# WordClock_LED_Display.net
KiCad netlist of a schematic drawn in Altium Designer
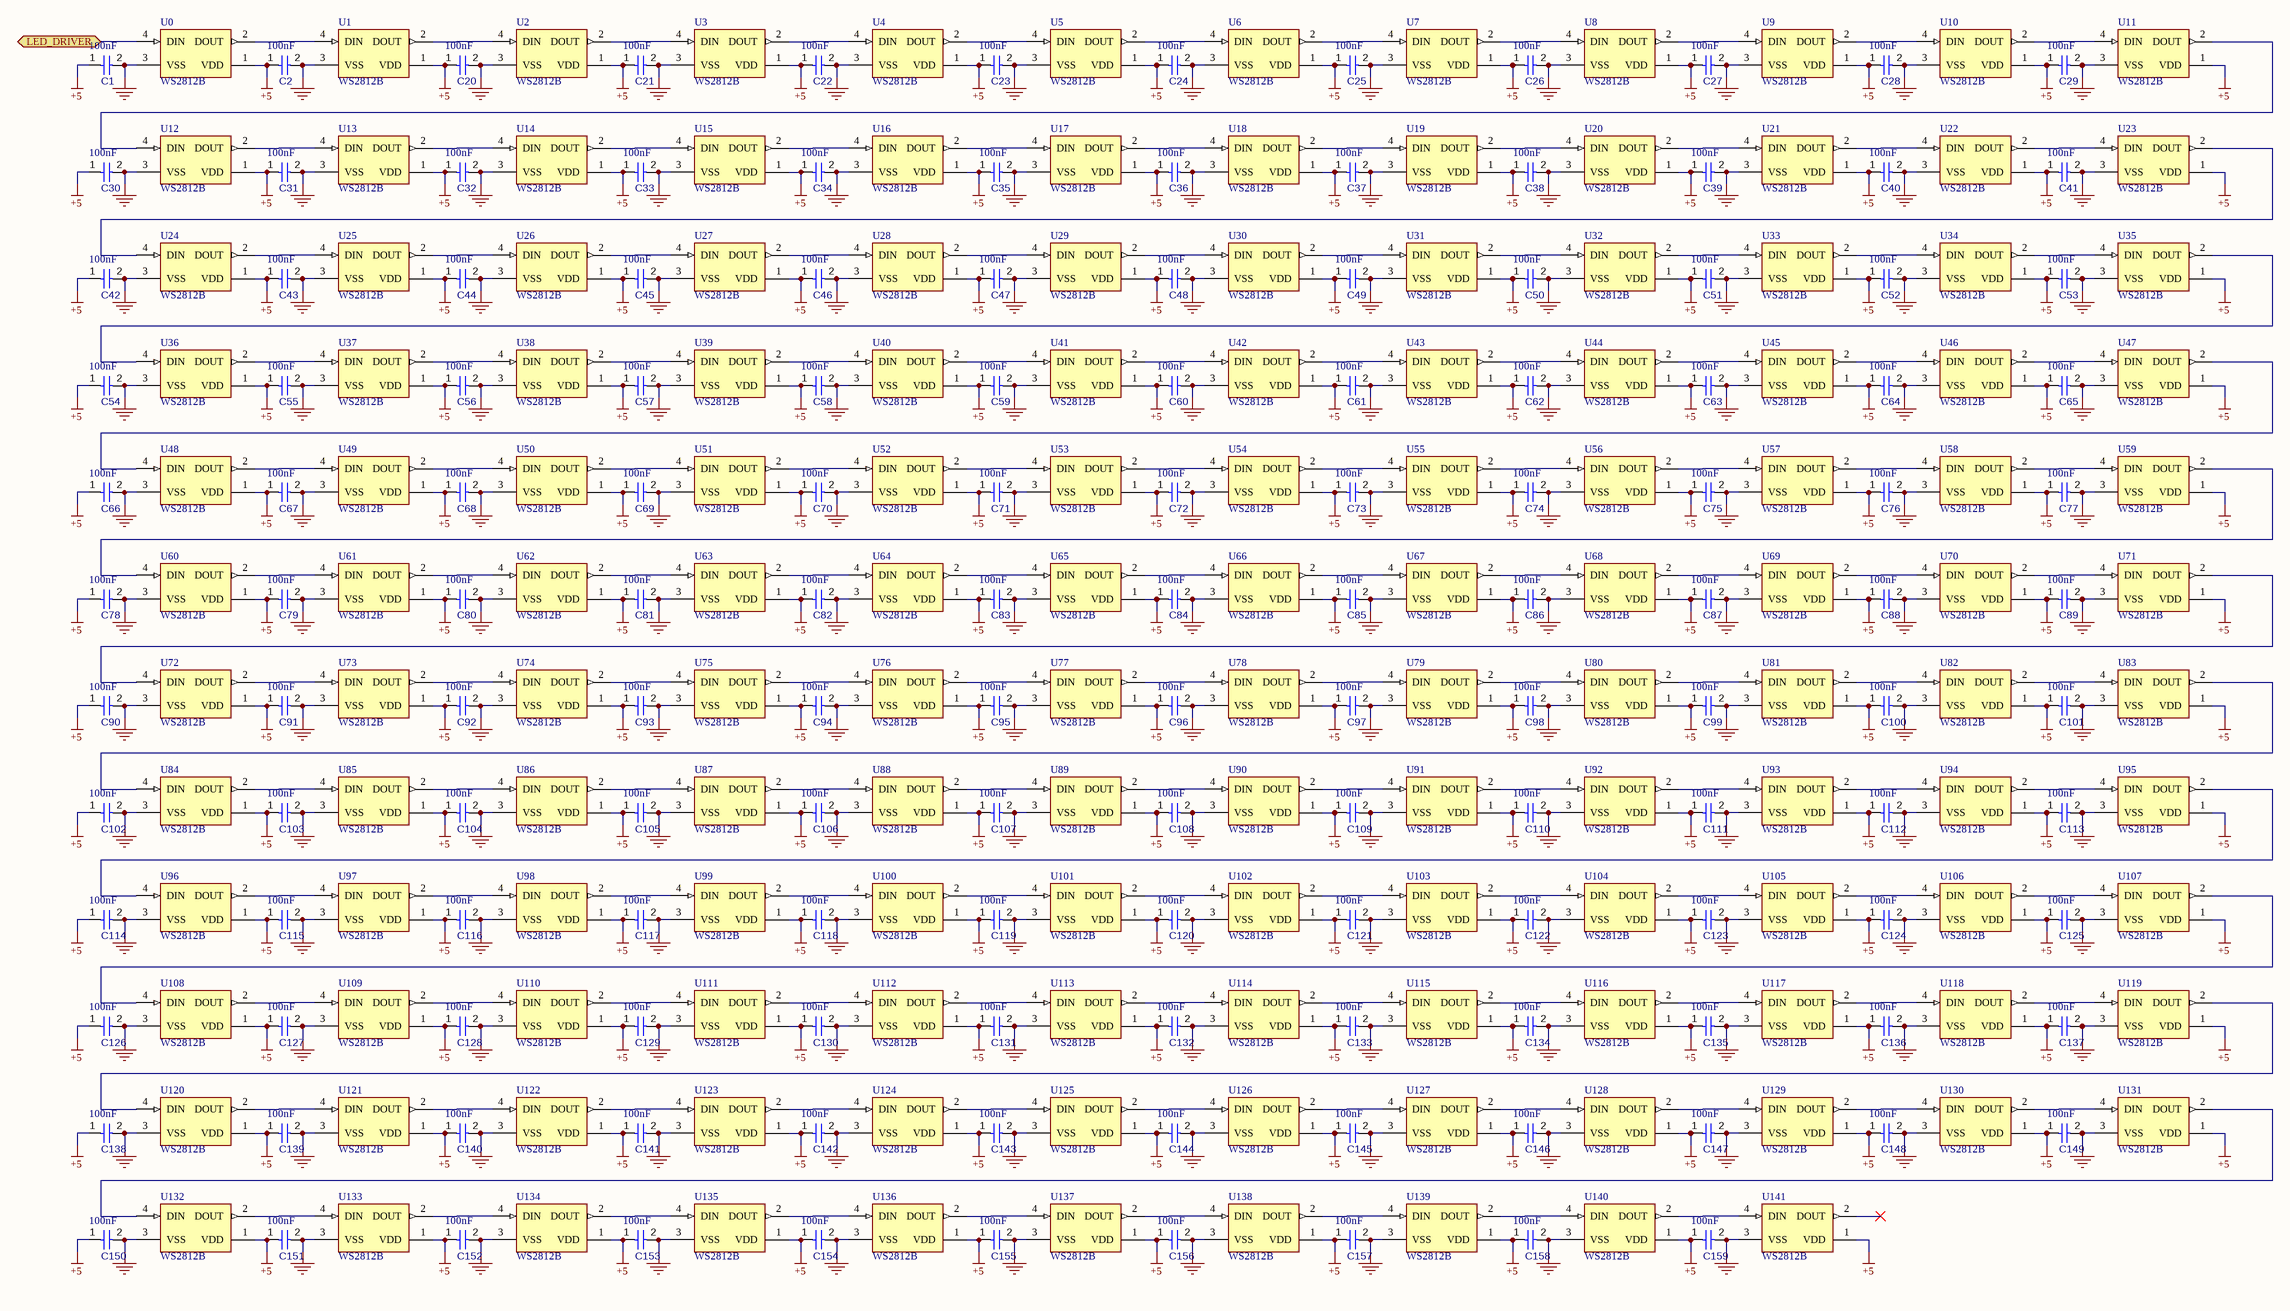
[diagram p0: WordClock_LED_Display.SchDoc]

(export (version "E")
  (design (tool "Eeschema 10.0.6"))
  (components
    (comp (ref "C1")
      (value "100nF")
      (footprint "CAPC0402(1005)60_L")
      (description "Chip Capacitor, 100nF +/-20%, 25V, 0402, Thickness 0.6 mm")
      (fields (field (name "TOLERANCE") "10%") (field (name "Comment") "Capacitor 100nF +/-20% 25V 0402"))
      (libsource (lib "Southwestern College") (part "CAP-NP-2"))
    )
    (comp (ref "C2")
      (value "100nF")
      (footprint "CAPC0402(1005)60_L")
      (description "Chip Capacitor, 100nF +/-20%, 25V, 0402, Thickness 0.6 mm")
      (fields (field (name "TOLERANCE") "10%") (field (name "Comment") "Capacitor 100nF +/-20% 25V 0402"))
      (libsource (lib "Southwestern College") (part "CAP-NP-2"))
    )
    (comp (ref "C20")
      (value "100nF")
      (footprint "CAPC0402(1005)60_L")
      (description "Chip Capacitor, 100nF +/-20%, 25V, 0402, Thickness 0.6 mm")
      (fields (field (name "TOLERANCE") "10%") (field (name "Comment") "Capacitor 100nF +/-20% 25V 0402"))
      (libsource (lib "Southwestern College") (part "CAP-NP-2"))
    )
    (comp (ref "C21")
      (value "100nF")
      (footprint "CAPC0402(1005)60_L")
      (description "Chip Capacitor, 100nF +/-20%, 25V, 0402, Thickness 0.6 mm")
      (fields (field (name "TOLERANCE") "10%") (field (name "Comment") "Capacitor 100nF +/-20% 25V 0402"))
      (libsource (lib "Southwestern College") (part "CAP-NP-2"))
    )
    (comp (ref "C22")
      (value "100nF")
      (footprint "CAPC0402(1005)60_L")
      (description "Chip Capacitor, 100nF +/-20%, 25V, 0402, Thickness 0.6 mm")
      (fields (field (name "TOLERANCE") "10%") (field (name "Comment") "Capacitor 100nF +/-20% 25V 0402"))
      (libsource (lib "Southwestern College") (part "CAP-NP-2"))
    )
    (comp (ref "C23")
      (value "100nF")
      (footprint "CAPC0402(1005)60_L")
      (description "Chip Capacitor, 100nF +/-20%, 25V, 0402, Thickness 0.6 mm")
      (fields (field (name "TOLERANCE") "10%") (field (name "Comment") "Capacitor 100nF +/-20% 25V 0402"))
      (libsource (lib "Southwestern College") (part "CAP-NP-2"))
    )
    (comp (ref "C24")
      (value "100nF")
      (footprint "CAPC0402(1005)60_L")
      (description "Chip Capacitor, 100nF +/-20%, 25V, 0402, Thickness 0.6 mm")
      (fields (field (name "TOLERANCE") "10%") (field (name "Comment") "Capacitor 100nF +/-20% 25V 0402"))
      (libsource (lib "Southwestern College") (part "CAP-NP-2"))
    )
    (comp (ref "C25")
      (value "100nF")
      (footprint "CAPC0402(1005)60_L")
      (description "Chip Capacitor, 100nF +/-20%, 25V, 0402, Thickness 0.6 mm")
      (fields (field (name "TOLERANCE") "10%") (field (name "Comment") "Capacitor 100nF +/-20% 25V 0402"))
      (libsource (lib "Southwestern College") (part "CAP-NP-2"))
    )
    (comp (ref "C26")
      (value "100nF")
      (footprint "CAPC0402(1005)60_L")
      (description "Chip Capacitor, 100nF +/-20%, 25V, 0402, Thickness 0.6 mm")
      (fields (field (name "TOLERANCE") "10%") (field (name "Comment") "Capacitor 100nF +/-20% 25V 0402"))
      (libsource (lib "Southwestern College") (part "CAP-NP-2"))
    )
    (comp (ref "C27")
      (value "100nF")
      (footprint "CAPC0402(1005)60_L")
      (description "Chip Capacitor, 100nF +/-20%, 25V, 0402, Thickness 0.6 mm")
      (fields (field (name "TOLERANCE") "10%") (field (name "Comment") "Capacitor 100nF +/-20% 25V 0402"))
      (libsource (lib "Southwestern College") (part "CAP-NP-2"))
    )
    (comp (ref "C28")
      (value "100nF")
      (footprint "CAPC0402(1005)60_L")
      (description "Chip Capacitor, 100nF +/-20%, 25V, 0402, Thickness 0.6 mm")
      (fields (field (name "TOLERANCE") "10%") (field (name "Comment") "Capacitor 100nF +/-20% 25V 0402"))
      (libsource (lib "Southwestern College") (part "CAP-NP-2"))
    )
    (comp (ref "C29")
      (value "100nF")
      (footprint "CAPC0402(1005)60_L")
      (description "Chip Capacitor, 100nF +/-20%, 25V, 0402, Thickness 0.6 mm")
      (fields (field (name "TOLERANCE") "10%") (field (name "Comment") "Capacitor 100nF +/-20% 25V 0402"))
      (libsource (lib "Southwestern College") (part "CAP-NP-2"))
    )
    (comp (ref "C30")
      (value "100nF")
      (footprint "CAPC0402(1005)60_L")
      (description "Chip Capacitor, 100nF +/-20%, 25V, 0402, Thickness 0.6 mm")
      (fields (field (name "TOLERANCE") "10%") (field (name "Comment") "Capacitor 100nF +/-20% 25V 0402"))
      (libsource (lib "Southwestern College") (part "CAP-NP-2"))
    )
    (comp (ref "C31")
      (value "100nF")
      (footprint "CAPC0402(1005)60_L")
      (description "Chip Capacitor, 100nF +/-20%, 25V, 0402, Thickness 0.6 mm")
      (fields (field (name "TOLERANCE") "10%") (field (name "Comment") "Capacitor 100nF +/-20% 25V 0402"))
      (libsource (lib "Southwestern College") (part "CAP-NP-2"))
    )
    (comp (ref "C32")
      (value "100nF")
      (footprint "CAPC0402(1005)60_L")
      (description "Chip Capacitor, 100nF +/-20%, 25V, 0402, Thickness 0.6 mm")
      (fields (field (name "TOLERANCE") "10%") (field (name "Comment") "Capacitor 100nF +/-20% 25V 0402"))
      (libsource (lib "Southwestern College") (part "CAP-NP-2"))
    )
    (comp (ref "C33")
      (value "100nF")
      (footprint "CAPC0402(1005)60_L")
      (description "Chip Capacitor, 100nF +/-20%, 25V, 0402, Thickness 0.6 mm")
      (fields (field (name "TOLERANCE") "10%") (field (name "Comment") "Capacitor 100nF +/-20% 25V 0402"))
      (libsource (lib "Southwestern College") (part "CAP-NP-2"))
    )
    (comp (ref "C34")
      (value "100nF")
      (footprint "CAPC0402(1005)60_L")
      (description "Chip Capacitor, 100nF +/-20%, 25V, 0402, Thickness 0.6 mm")
      (fields (field (name "TOLERANCE") "10%") (field (name "Comment") "Capacitor 100nF +/-20% 25V 0402"))
      (libsource (lib "Southwestern College") (part "CAP-NP-2"))
    )
    (comp (ref "C35")
      (value "100nF")
      (footprint "CAPC0402(1005)60_L")
      (description "Chip Capacitor, 100nF +/-20%, 25V, 0402, Thickness 0.6 mm")
      (fields (field (name "TOLERANCE") "10%") (field (name "Comment") "Capacitor 100nF +/-20% 25V 0402"))
      (libsource (lib "Southwestern College") (part "CAP-NP-2"))
    )
    (comp (ref "C36")
      (value "100nF")
      (footprint "CAPC0402(1005)60_L")
      (description "Chip Capacitor, 100nF +/-20%, 25V, 0402, Thickness 0.6 mm")
      (fields (field (name "TOLERANCE") "10%") (field (name "Comment") "Capacitor 100nF +/-20% 25V 0402"))
      (libsource (lib "Southwestern College") (part "CAP-NP-2"))
    )
    (comp (ref "C37")
      (value "100nF")
      (footprint "CAPC0402(1005)60_L")
      (description "Chip Capacitor, 100nF +/-20%, 25V, 0402, Thickness 0.6 mm")
      (fields (field (name "TOLERANCE") "10%") (field (name "Comment") "Capacitor 100nF +/-20% 25V 0402"))
      (libsource (lib "Southwestern College") (part "CAP-NP-2"))
    )
    (comp (ref "C38")
      (value "100nF")
      (footprint "CAPC0402(1005)60_L")
      (description "Chip Capacitor, 100nF +/-20%, 25V, 0402, Thickness 0.6 mm")
      (fields (field (name "TOLERANCE") "10%") (field (name "Comment") "Capacitor 100nF +/-20% 25V 0402"))
      (libsource (lib "Southwestern College") (part "CAP-NP-2"))
    )
    (comp (ref "C39")
      (value "100nF")
      (footprint "CAPC0402(1005)60_L")
      (description "Chip Capacitor, 100nF +/-20%, 25V, 0402, Thickness 0.6 mm")
      (fields (field (name "TOLERANCE") "10%") (field (name "Comment") "Capacitor 100nF +/-20% 25V 0402"))
      (libsource (lib "Southwestern College") (part "CAP-NP-2"))
    )
    (comp (ref "C40")
      (value "100nF")
      (footprint "CAPC0402(1005)60_L")
      (description "Chip Capacitor, 100nF +/-20%, 25V, 0402, Thickness 0.6 mm")
      (fields (field (name "TOLERANCE") "10%") (field (name "Comment") "Capacitor 100nF +/-20% 25V 0402"))
      (libsource (lib "Southwestern College") (part "CAP-NP-2"))
    )
    (comp (ref "C41")
      (value "100nF")
      (footprint "CAPC0402(1005)60_L")
      (description "Chip Capacitor, 100nF +/-20%, 25V, 0402, Thickness 0.6 mm")
      (fields (field (name "TOLERANCE") "10%") (field (name "Comment") "Capacitor 100nF +/-20% 25V 0402"))
      (libsource (lib "Southwestern College") (part "CAP-NP-2"))
    )
    (comp (ref "C42")
      (value "100nF")
      (footprint "CAPC0402(1005)60_L")
      (description "Chip Capacitor, 100nF +/-20%, 25V, 0402, Thickness 0.6 mm")
      (fields (field (name "TOLERANCE") "10%") (field (name "Comment") "Capacitor 100nF +/-20% 25V 0402"))
      (libsource (lib "Southwestern College") (part "CAP-NP-2"))
    )
    (comp (ref "C43")
      (value "100nF")
      (footprint "CAPC0402(1005)60_L")
      (description "Chip Capacitor, 100nF +/-20%, 25V, 0402, Thickness 0.6 mm")
      (fields (field (name "TOLERANCE") "10%") (field (name "Comment") "Capacitor 100nF +/-20% 25V 0402"))
      (libsource (lib "Southwestern College") (part "CAP-NP-2"))
    )
    (comp (ref "C44")
      (value "100nF")
      (footprint "CAPC0402(1005)60_L")
      (description "Chip Capacitor, 100nF +/-20%, 25V, 0402, Thickness 0.6 mm")
      (fields (field (name "TOLERANCE") "10%") (field (name "Comment") "Capacitor 100nF +/-20% 25V 0402"))
      (libsource (lib "Southwestern College") (part "CAP-NP-2"))
    )
    (comp (ref "C45")
      (value "100nF")
      (footprint "CAPC0402(1005)60_L")
      (description "Chip Capacitor, 100nF +/-20%, 25V, 0402, Thickness 0.6 mm")
      (fields (field (name "TOLERANCE") "10%") (field (name "Comment") "Capacitor 100nF +/-20% 25V 0402"))
      (libsource (lib "Southwestern College") (part "CAP-NP-2"))
    )
    (comp (ref "C46")
      (value "100nF")
      (footprint "CAPC0402(1005)60_L")
      (description "Chip Capacitor, 100nF +/-20%, 25V, 0402, Thickness 0.6 mm")
      (fields (field (name "TOLERANCE") "10%") (field (name "Comment") "Capacitor 100nF +/-20% 25V 0402"))
      (libsource (lib "Southwestern College") (part "CAP-NP-2"))
    )
    (comp (ref "C47")
      (value "100nF")
      (footprint "CAPC0402(1005)60_L")
      (description "Chip Capacitor, 100nF +/-20%, 25V, 0402, Thickness 0.6 mm")
      (fields (field (name "TOLERANCE") "10%") (field (name "Comment") "Capacitor 100nF +/-20% 25V 0402"))
      (libsource (lib "Southwestern College") (part "CAP-NP-2"))
    )
    (comp (ref "C48")
      (value "100nF")
      (footprint "CAPC0402(1005)60_L")
      (description "Chip Capacitor, 100nF +/-20%, 25V, 0402, Thickness 0.6 mm")
      (fields (field (name "TOLERANCE") "10%") (field (name "Comment") "Capacitor 100nF +/-20% 25V 0402"))
      (libsource (lib "Southwestern College") (part "CAP-NP-2"))
    )
    (comp (ref "C49")
      (value "100nF")
      (footprint "CAPC0402(1005)60_L")
      (description "Chip Capacitor, 100nF +/-20%, 25V, 0402, Thickness 0.6 mm")
      (fields (field (name "TOLERANCE") "10%") (field (name "Comment") "Capacitor 100nF +/-20% 25V 0402"))
      (libsource (lib "Southwestern College") (part "CAP-NP-2"))
    )
    (comp (ref "C50")
      (value "100nF")
      (footprint "CAPC0402(1005)60_L")
      (description "Chip Capacitor, 100nF +/-20%, 25V, 0402, Thickness 0.6 mm")
      (fields (field (name "TOLERANCE") "10%") (field (name "Comment") "Capacitor 100nF +/-20% 25V 0402"))
      (libsource (lib "Southwestern College") (part "CAP-NP-2"))
    )
    (comp (ref "C51")
      (value "100nF")
      (footprint "CAPC0402(1005)60_L")
      (description "Chip Capacitor, 100nF +/-20%, 25V, 0402, Thickness 0.6 mm")
      (fields (field (name "TOLERANCE") "10%") (field (name "Comment") "Capacitor 100nF +/-20% 25V 0402"))
      (libsource (lib "Southwestern College") (part "CAP-NP-2"))
    )
    (comp (ref "C52")
      (value "100nF")
      (footprint "CAPC0402(1005)60_L")
      (description "Chip Capacitor, 100nF +/-20%, 25V, 0402, Thickness 0.6 mm")
      (fields (field (name "TOLERANCE") "10%") (field (name "Comment") "Capacitor 100nF +/-20% 25V 0402"))
      (libsource (lib "Southwestern College") (part "CAP-NP-2"))
    )
    (comp (ref "C53")
      (value "100nF")
      (footprint "CAPC0402(1005)60_L")
      (description "Chip Capacitor, 100nF +/-20%, 25V, 0402, Thickness 0.6 mm")
      (fields (field (name "TOLERANCE") "10%") (field (name "Comment") "Capacitor 100nF +/-20% 25V 0402"))
      (libsource (lib "Southwestern College") (part "CAP-NP-2"))
    )
    (comp (ref "C54")
      (value "100nF")
      (footprint "CAPC0402(1005)60_L")
      (description "Chip Capacitor, 100nF +/-20%, 25V, 0402, Thickness 0.6 mm")
      (fields (field (name "TOLERANCE") "10%") (field (name "Comment") "Capacitor 100nF +/-20% 25V 0402"))
      (libsource (lib "Southwestern College") (part "CAP-NP-2"))
    )
    (comp (ref "C55")
      (value "100nF")
      (footprint "CAPC0402(1005)60_L")
      (description "Chip Capacitor, 100nF +/-20%, 25V, 0402, Thickness 0.6 mm")
      (fields (field (name "TOLERANCE") "10%") (field (name "Comment") "Capacitor 100nF +/-20% 25V 0402"))
      (libsource (lib "Southwestern College") (part "CAP-NP-2"))
    )
    (comp (ref "C56")
      (value "100nF")
      (footprint "CAPC0402(1005)60_L")
      (description "Chip Capacitor, 100nF +/-20%, 25V, 0402, Thickness 0.6 mm")
      (fields (field (name "TOLERANCE") "10%") (field (name "Comment") "Capacitor 100nF +/-20% 25V 0402"))
      (libsource (lib "Southwestern College") (part "CAP-NP-2"))
    )
    (comp (ref "C57")
      (value "100nF")
      (footprint "CAPC0402(1005)60_L")
      (description "Chip Capacitor, 100nF +/-20%, 25V, 0402, Thickness 0.6 mm")
      (fields (field (name "TOLERANCE") "10%") (field (name "Comment") "Capacitor 100nF +/-20% 25V 0402"))
      (libsource (lib "Southwestern College") (part "CAP-NP-2"))
    )
    (comp (ref "C58")
      (value "100nF")
      (footprint "CAPC0402(1005)60_L")
      (description "Chip Capacitor, 100nF +/-20%, 25V, 0402, Thickness 0.6 mm")
      (fields (field (name "TOLERANCE") "10%") (field (name "Comment") "Capacitor 100nF +/-20% 25V 0402"))
      (libsource (lib "Southwestern College") (part "CAP-NP-2"))
    )
    (comp (ref "C59")
      (value "100nF")
      (footprint "CAPC0402(1005)60_L")
      (description "Chip Capacitor, 100nF +/-20%, 25V, 0402, Thickness 0.6 mm")
      (fields (field (name "TOLERANCE") "10%") (field (name "Comment") "Capacitor 100nF +/-20% 25V 0402"))
      (libsource (lib "Southwestern College") (part "CAP-NP-2"))
    )
    (comp (ref "C60")
      (value "100nF")
      (footprint "CAPC0402(1005)60_L")
      (description "Chip Capacitor, 100nF +/-20%, 25V, 0402, Thickness 0.6 mm")
      (fields (field (name "TOLERANCE") "10%") (field (name "Comment") "Capacitor 100nF +/-20% 25V 0402"))
      (libsource (lib "Southwestern College") (part "CAP-NP-2"))
    )
    (comp (ref "C61")
      (value "100nF")
      (footprint "CAPC0402(1005)60_L")
      (description "Chip Capacitor, 100nF +/-20%, 25V, 0402, Thickness 0.6 mm")
      (fields (field (name "TOLERANCE") "10%") (field (name "Comment") "Capacitor 100nF +/-20% 25V 0402"))
      (libsource (lib "Southwestern College") (part "CAP-NP-2"))
    )
    (comp (ref "C62")
      (value "100nF")
      (footprint "CAPC0402(1005)60_L")
      (description "Chip Capacitor, 100nF +/-20%, 25V, 0402, Thickness 0.6 mm")
      (fields (field (name "TOLERANCE") "10%") (field (name "Comment") "Capacitor 100nF +/-20% 25V 0402"))
      (libsource (lib "Southwestern College") (part "CAP-NP-2"))
    )
    (comp (ref "C63")
      (value "100nF")
      (footprint "CAPC0402(1005)60_L")
      (description "Chip Capacitor, 100nF +/-20%, 25V, 0402, Thickness 0.6 mm")
      (fields (field (name "TOLERANCE") "10%") (field (name "Comment") "Capacitor 100nF +/-20% 25V 0402"))
      (libsource (lib "Southwestern College") (part "CAP-NP-2"))
    )
    (comp (ref "C64")
      (value "100nF")
      (footprint "CAPC0402(1005)60_L")
      (description "Chip Capacitor, 100nF +/-20%, 25V, 0402, Thickness 0.6 mm")
      (fields (field (name "TOLERANCE") "10%") (field (name "Comment") "Capacitor 100nF +/-20% 25V 0402"))
      (libsource (lib "Southwestern College") (part "CAP-NP-2"))
    )
    (comp (ref "C65")
      (value "100nF")
      (footprint "CAPC0402(1005)60_L")
      (description "Chip Capacitor, 100nF +/-20%, 25V, 0402, Thickness 0.6 mm")
      (fields (field (name "TOLERANCE") "10%") (field (name "Comment") "Capacitor 100nF +/-20% 25V 0402"))
      (libsource (lib "Southwestern College") (part "CAP-NP-2"))
    )
    (comp (ref "C66")
      (value "100nF")
      (footprint "CAPC0402(1005)60_L")
      (description "Chip Capacitor, 100nF +/-20%, 25V, 0402, Thickness 0.6 mm")
      (fields (field (name "TOLERANCE") "10%") (field (name "Comment") "Capacitor 100nF +/-20% 25V 0402"))
      (libsource (lib "Southwestern College") (part "CAP-NP-2"))
    )
    (comp (ref "C67")
      (value "100nF")
      (footprint "CAPC0402(1005)60_L")
      (description "Chip Capacitor, 100nF +/-20%, 25V, 0402, Thickness 0.6 mm")
      (fields (field (name "TOLERANCE") "10%") (field (name "Comment") "Capacitor 100nF +/-20% 25V 0402"))
      (libsource (lib "Southwestern College") (part "CAP-NP-2"))
    )
    (comp (ref "C68")
      (value "100nF")
      (footprint "CAPC0402(1005)60_L")
      (description "Chip Capacitor, 100nF +/-20%, 25V, 0402, Thickness 0.6 mm")
      (fields (field (name "TOLERANCE") "10%") (field (name "Comment") "Capacitor 100nF +/-20% 25V 0402"))
      (libsource (lib "Southwestern College") (part "CAP-NP-2"))
    )
    (comp (ref "C69")
      (value "100nF")
      (footprint "CAPC0402(1005)60_L")
      (description "Chip Capacitor, 100nF +/-20%, 25V, 0402, Thickness 0.6 mm")
      (fields (field (name "TOLERANCE") "10%") (field (name "Comment") "Capacitor 100nF +/-20% 25V 0402"))
      (libsource (lib "Southwestern College") (part "CAP-NP-2"))
    )
    (comp (ref "C70")
      (value "100nF")
      (footprint "CAPC0402(1005)60_L")
      (description "Chip Capacitor, 100nF +/-20%, 25V, 0402, Thickness 0.6 mm")
      (fields (field (name "TOLERANCE") "10%") (field (name "Comment") "Capacitor 100nF +/-20% 25V 0402"))
      (libsource (lib "Southwestern College") (part "CAP-NP-2"))
    )
    (comp (ref "C71")
      (value "100nF")
      (footprint "CAPC0402(1005)60_L")
      (description "Chip Capacitor, 100nF +/-20%, 25V, 0402, Thickness 0.6 mm")
      (fields (field (name "TOLERANCE") "10%") (field (name "Comment") "Capacitor 100nF +/-20% 25V 0402"))
      (libsource (lib "Southwestern College") (part "CAP-NP-2"))
    )
    (comp (ref "C72")
      (value "100nF")
      (footprint "CAPC0402(1005)60_L")
      (description "Chip Capacitor, 100nF +/-20%, 25V, 0402, Thickness 0.6 mm")
      (fields (field (name "TOLERANCE") "10%") (field (name "Comment") "Capacitor 100nF +/-20% 25V 0402"))
      (libsource (lib "Southwestern College") (part "CAP-NP-2"))
    )
    (comp (ref "C73")
      (value "100nF")
      (footprint "CAPC0402(1005)60_L")
      (description "Chip Capacitor, 100nF +/-20%, 25V, 0402, Thickness 0.6 mm")
      (fields (field (name "TOLERANCE") "10%") (field (name "Comment") "Capacitor 100nF +/-20% 25V 0402"))
      (libsource (lib "Southwestern College") (part "CAP-NP-2"))
    )
    (comp (ref "C74")
      (value "100nF")
      (footprint "CAPC0402(1005)60_L")
      (description "Chip Capacitor, 100nF +/-20%, 25V, 0402, Thickness 0.6 mm")
      (fields (field (name "TOLERANCE") "10%") (field (name "Comment") "Capacitor 100nF +/-20% 25V 0402"))
      (libsource (lib "Southwestern College") (part "CAP-NP-2"))
    )
    (comp (ref "C75")
      (value "100nF")
      (footprint "CAPC0402(1005)60_L")
      (description "Chip Capacitor, 100nF +/-20%, 25V, 0402, Thickness 0.6 mm")
      (fields (field (name "TOLERANCE") "10%") (field (name "Comment") "Capacitor 100nF +/-20% 25V 0402"))
      (libsource (lib "Southwestern College") (part "CAP-NP-2"))
    )
    (comp (ref "C76")
      (value "100nF")
      (footprint "CAPC0402(1005)60_L")
      (description "Chip Capacitor, 100nF +/-20%, 25V, 0402, Thickness 0.6 mm")
      (fields (field (name "TOLERANCE") "10%") (field (name "Comment") "Capacitor 100nF +/-20% 25V 0402"))
      (libsource (lib "Southwestern College") (part "CAP-NP-2"))
    )
    (comp (ref "C77")
      (value "100nF")
      (footprint "CAPC0402(1005)60_L")
      (description "Chip Capacitor, 100nF +/-20%, 25V, 0402, Thickness 0.6 mm")
      (fields (field (name "TOLERANCE") "10%") (field (name "Comment") "Capacitor 100nF +/-20% 25V 0402"))
      (libsource (lib "Southwestern College") (part "CAP-NP-2"))
    )
    (comp (ref "C78")
      (value "100nF")
      (footprint "CAPC0402(1005)60_L")
      (description "Chip Capacitor, 100nF +/-20%, 25V, 0402, Thickness 0.6 mm")
      (fields (field (name "TOLERANCE") "10%") (field (name "Comment") "Capacitor 100nF +/-20% 25V 0402"))
      (libsource (lib "Southwestern College") (part "CAP-NP-2"))
    )
    (comp (ref "C79")
      (value "100nF")
      (footprint "CAPC0402(1005)60_L")
      (description "Chip Capacitor, 100nF +/-20%, 25V, 0402, Thickness 0.6 mm")
      (fields (field (name "TOLERANCE") "10%") (field (name "Comment") "Capacitor 100nF +/-20% 25V 0402"))
      (libsource (lib "Southwestern College") (part "CAP-NP-2"))
    )
    (comp (ref "C80")
      (value "100nF")
      (footprint "CAPC0402(1005)60_L")
      (description "Chip Capacitor, 100nF +/-20%, 25V, 0402, Thickness 0.6 mm")
      (fields (field (name "TOLERANCE") "10%") (field (name "Comment") "Capacitor 100nF +/-20% 25V 0402"))
      (libsource (lib "Southwestern College") (part "CAP-NP-2"))
    )
    (comp (ref "C81")
      (value "100nF")
      (footprint "CAPC0402(1005)60_L")
      (description "Chip Capacitor, 100nF +/-20%, 25V, 0402, Thickness 0.6 mm")
      (fields (field (name "TOLERANCE") "10%") (field (name "Comment") "Capacitor 100nF +/-20% 25V 0402"))
      (libsource (lib "Southwestern College") (part "CAP-NP-2"))
    )
    (comp (ref "C82")
      (value "100nF")
      (footprint "CAPC0402(1005)60_L")
      (description "Chip Capacitor, 100nF +/-20%, 25V, 0402, Thickness 0.6 mm")
      (fields (field (name "TOLERANCE") "10%") (field (name "Comment") "Capacitor 100nF +/-20% 25V 0402"))
      (libsource (lib "Southwestern College") (part "CAP-NP-2"))
    )
    (comp (ref "C83")
      (value "100nF")
      (footprint "CAPC0402(1005)60_L")
      (description "Chip Capacitor, 100nF +/-20%, 25V, 0402, Thickness 0.6 mm")
      (fields (field (name "TOLERANCE") "10%") (field (name "Comment") "Capacitor 100nF +/-20% 25V 0402"))
      (libsource (lib "Southwestern College") (part "CAP-NP-2"))
    )
    (comp (ref "C84")
      (value "100nF")
      (footprint "CAPC0402(1005)60_L")
      (description "Chip Capacitor, 100nF +/-20%, 25V, 0402, Thickness 0.6 mm")
      (fields (field (name "TOLERANCE") "10%") (field (name "Comment") "Capacitor 100nF +/-20% 25V 0402"))
      (libsource (lib "Southwestern College") (part "CAP-NP-2"))
    )
    (comp (ref "C85")
      (value "100nF")
      (footprint "CAPC0402(1005)60_L")
      (description "Chip Capacitor, 100nF +/-20%, 25V, 0402, Thickness 0.6 mm")
      (fields (field (name "TOLERANCE") "10%") (field (name "Comment") "Capacitor 100nF +/-20% 25V 0402"))
      (libsource (lib "Southwestern College") (part "CAP-NP-2"))
    )
    (comp (ref "C86")
      (value "100nF")
      (footprint "CAPC0402(1005)60_L")
      (description "Chip Capacitor, 100nF +/-20%, 25V, 0402, Thickness 0.6 mm")
      (fields (field (name "TOLERANCE") "10%") (field (name "Comment") "Capacitor 100nF +/-20% 25V 0402"))
      (libsource (lib "Southwestern College") (part "CAP-NP-2"))
    )
    (comp (ref "C87")
      (value "100nF")
      (footprint "CAPC0402(1005)60_L")
      (description "Chip Capacitor, 100nF +/-20%, 25V, 0402, Thickness 0.6 mm")
      (fields (field (name "TOLERANCE") "10%") (field (name "Comment") "Capacitor 100nF +/-20% 25V 0402"))
      (libsource (lib "Southwestern College") (part "CAP-NP-2"))
    )
    (comp (ref "C88")
      (value "100nF")
      (footprint "CAPC0402(1005)60_L")
      (description "Chip Capacitor, 100nF +/-20%, 25V, 0402, Thickness 0.6 mm")
      (fields (field (name "TOLERANCE") "10%") (field (name "Comment") "Capacitor 100nF +/-20% 25V 0402"))
      (libsource (lib "Southwestern College") (part "CAP-NP-2"))
    )
    (comp (ref "C89")
      (value "100nF")
      (footprint "CAPC0402(1005)60_L")
      (description "Chip Capacitor, 100nF +/-20%, 25V, 0402, Thickness 0.6 mm")
      (fields (field (name "TOLERANCE") "10%") (field (name "Comment") "Capacitor 100nF +/-20% 25V 0402"))
      (libsource (lib "Southwestern College") (part "CAP-NP-2"))
    )
    (comp (ref "C90")
      (value "100nF")
      (footprint "CAPC0402(1005)60_L")
      (description "Chip Capacitor, 100nF +/-20%, 25V, 0402, Thickness 0.6 mm")
      (fields (field (name "TOLERANCE") "10%") (field (name "Comment") "Capacitor 100nF +/-20% 25V 0402"))
      (libsource (lib "Southwestern College") (part "CAP-NP-2"))
    )
    (comp (ref "C91")
      (value "100nF")
      (footprint "CAPC0402(1005)60_L")
      (description "Chip Capacitor, 100nF +/-20%, 25V, 0402, Thickness 0.6 mm")
      (fields (field (name "TOLERANCE") "10%") (field (name "Comment") "Capacitor 100nF +/-20% 25V 0402"))
      (libsource (lib "Southwestern College") (part "CAP-NP-2"))
    )
    (comp (ref "C92")
      (value "100nF")
      (footprint "CAPC0402(1005)60_L")
      (description "Chip Capacitor, 100nF +/-20%, 25V, 0402, Thickness 0.6 mm")
      (fields (field (name "TOLERANCE") "10%") (field (name "Comment") "Capacitor 100nF +/-20% 25V 0402"))
      (libsource (lib "Southwestern College") (part "CAP-NP-2"))
    )
    (comp (ref "C93")
      (value "100nF")
      (footprint "CAPC0402(1005)60_L")
      (description "Chip Capacitor, 100nF +/-20%, 25V, 0402, Thickness 0.6 mm")
      (fields (field (name "TOLERANCE") "10%") (field (name "Comment") "Capacitor 100nF +/-20% 25V 0402"))
      (libsource (lib "Southwestern College") (part "CAP-NP-2"))
    )
    (comp (ref "C94")
      (value "100nF")
      (footprint "CAPC0402(1005)60_L")
      (description "Chip Capacitor, 100nF +/-20%, 25V, 0402, Thickness 0.6 mm")
      (fields (field (name "TOLERANCE") "10%") (field (name "Comment") "Capacitor 100nF +/-20% 25V 0402"))
      (libsource (lib "Southwestern College") (part "CAP-NP-2"))
    )
    (comp (ref "C95")
      (value "100nF")
      (footprint "CAPC0402(1005)60_L")
      (description "Chip Capacitor, 100nF +/-20%, 25V, 0402, Thickness 0.6 mm")
      (fields (field (name "TOLERANCE") "10%") (field (name "Comment") "Capacitor 100nF +/-20% 25V 0402"))
      (libsource (lib "Southwestern College") (part "CAP-NP-2"))
    )
    (comp (ref "C96")
      (value "100nF")
      (footprint "CAPC0402(1005)60_L")
      (description "Chip Capacitor, 100nF +/-20%, 25V, 0402, Thickness 0.6 mm")
      (fields (field (name "TOLERANCE") "10%") (field (name "Comment") "Capacitor 100nF +/-20% 25V 0402"))
      (libsource (lib "Southwestern College") (part "CAP-NP-2"))
    )
    (comp (ref "C97")
      (value "100nF")
      (footprint "CAPC0402(1005)60_L")
      (description "Chip Capacitor, 100nF +/-20%, 25V, 0402, Thickness 0.6 mm")
      (fields (field (name "TOLERANCE") "10%") (field (name "Comment") "Capacitor 100nF +/-20% 25V 0402"))
      (libsource (lib "Southwestern College") (part "CAP-NP-2"))
    )
    (comp (ref "C98")
      (value "100nF")
      (footprint "CAPC0402(1005)60_L")
      (description "Chip Capacitor, 100nF +/-20%, 25V, 0402, Thickness 0.6 mm")
      (fields (field (name "TOLERANCE") "10%") (field (name "Comment") "Capacitor 100nF +/-20% 25V 0402"))
      (libsource (lib "Southwestern College") (part "CAP-NP-2"))
    )
    (comp (ref "C99")
      (value "100nF")
      (footprint "CAPC0402(1005)60_L")
      (description "Chip Capacitor, 100nF +/-20%, 25V, 0402, Thickness 0.6 mm")
      (fields (field (name "TOLERANCE") "10%") (field (name "Comment") "Capacitor 100nF +/-20% 25V 0402"))
      (libsource (lib "Southwestern College") (part "CAP-NP-2"))
    )
    (comp (ref "C100")
      (value "100nF")
      (footprint "CAPC0402(1005)60_L")
      (description "Chip Capacitor, 100nF +/-20%, 25V, 0402, Thickness 0.6 mm")
      (fields (field (name "TOLERANCE") "10%") (field (name "Comment") "Capacitor 100nF +/-20% 25V 0402"))
      (libsource (lib "Southwestern College") (part "CAP-NP-2"))
    )
    (comp (ref "C101")
      (value "100nF")
      (footprint "CAPC0402(1005)60_L")
      (description "Chip Capacitor, 100nF +/-20%, 25V, 0402, Thickness 0.6 mm")
      (fields (field (name "TOLERANCE") "10%") (field (name "Comment") "Capacitor 100nF +/-20% 25V 0402"))
      (libsource (lib "Southwestern College") (part "CAP-NP-2"))
    )
    (comp (ref "C102")
      (value "100nF")
      (footprint "CAPC0402(1005)60_L")
      (description "Chip Capacitor, 100nF +/-20%, 25V, 0402, Thickness 0.6 mm")
      (fields (field (name "TOLERANCE") "10%") (field (name "Comment") "Capacitor 100nF +/-20% 25V 0402"))
      (libsource (lib "Southwestern College") (part "CAP-NP-2"))
    )
    (comp (ref "C103")
      (value "100nF")
      (footprint "CAPC0402(1005)60_L")
      (description "Chip Capacitor, 100nF +/-20%, 25V, 0402, Thickness 0.6 mm")
      (fields (field (name "TOLERANCE") "10%") (field (name "Comment") "Capacitor 100nF +/-20% 25V 0402"))
      (libsource (lib "Southwestern College") (part "CAP-NP-2"))
    )
    (comp (ref "C104")
      (value "100nF")
      (footprint "CAPC0402(1005)60_L")
      (description "Chip Capacitor, 100nF +/-20%, 25V, 0402, Thickness 0.6 mm")
      (fields (field (name "TOLERANCE") "10%") (field (name "Comment") "Capacitor 100nF +/-20% 25V 0402"))
      (libsource (lib "Southwestern College") (part "CAP-NP-2"))
    )
    (comp (ref "C105")
      (value "100nF")
      (footprint "CAPC0402(1005)60_L")
      (description "Chip Capacitor, 100nF +/-20%, 25V, 0402, Thickness 0.6 mm")
      (fields (field (name "TOLERANCE") "10%") (field (name "Comment") "Capacitor 100nF +/-20% 25V 0402"))
      (libsource (lib "Southwestern College") (part "CAP-NP-2"))
    )
    (comp (ref "C106")
      (value "100nF")
      (footprint "CAPC0402(1005)60_L")
      (description "Chip Capacitor, 100nF +/-20%, 25V, 0402, Thickness 0.6 mm")
      (fields (field (name "TOLERANCE") "10%") (field (name "Comment") "Capacitor 100nF +/-20% 25V 0402"))
      (libsource (lib "Southwestern College") (part "CAP-NP-2"))
    )
    (comp (ref "C107")
      (value "100nF")
      (footprint "CAPC0402(1005)60_L")
      (description "Chip Capacitor, 100nF +/-20%, 25V, 0402, Thickness 0.6 mm")
      (fields (field (name "TOLERANCE") "10%") (field (name "Comment") "Capacitor 100nF +/-20% 25V 0402"))
      (libsource (lib "Southwestern College") (part "CAP-NP-2"))
    )
    (comp (ref "C108")
      (value "100nF")
      (footprint "CAPC0402(1005)60_L")
      (description "Chip Capacitor, 100nF +/-20%, 25V, 0402, Thickness 0.6 mm")
      (fields (field (name "TOLERANCE") "10%") (field (name "Comment") "Capacitor 100nF +/-20% 25V 0402"))
      (libsource (lib "Southwestern College") (part "CAP-NP-2"))
    )
    (comp (ref "C109")
      (value "100nF")
      (footprint "CAPC0402(1005)60_L")
      (description "Chip Capacitor, 100nF +/-20%, 25V, 0402, Thickness 0.6 mm")
      (fields (field (name "TOLERANCE") "10%") (field (name "Comment") "Capacitor 100nF +/-20% 25V 0402"))
      (libsource (lib "Southwestern College") (part "CAP-NP-2"))
    )
    (comp (ref "C110")
      (value "100nF")
      (footprint "CAPC0402(1005)60_L")
      (description "Chip Capacitor, 100nF +/-20%, 25V, 0402, Thickness 0.6 mm")
      (fields (field (name "TOLERANCE") "10%") (field (name "Comment") "Capacitor 100nF +/-20% 25V 0402"))
      (libsource (lib "Southwestern College") (part "CAP-NP-2"))
    )
    (comp (ref "C111")
      (value "100nF")
      (footprint "CAPC0402(1005)60_L")
      (description "Chip Capacitor, 100nF +/-20%, 25V, 0402, Thickness 0.6 mm")
      (fields (field (name "TOLERANCE") "10%") (field (name "Comment") "Capacitor 100nF +/-20% 25V 0402"))
      (libsource (lib "Southwestern College") (part "CAP-NP-2"))
    )
    (comp (ref "C112")
      (value "100nF")
      (footprint "CAPC0402(1005)60_L")
      (description "Chip Capacitor, 100nF +/-20%, 25V, 0402, Thickness 0.6 mm")
      (fields (field (name "TOLERANCE") "10%") (field (name "Comment") "Capacitor 100nF +/-20% 25V 0402"))
      (libsource (lib "Southwestern College") (part "CAP-NP-2"))
    )
    (comp (ref "C113")
      (value "100nF")
      (footprint "CAPC0402(1005)60_L")
      (description "Chip Capacitor, 100nF +/-20%, 25V, 0402, Thickness 0.6 mm")
      (fields (field (name "TOLERANCE") "10%") (field (name "Comment") "Capacitor 100nF +/-20% 25V 0402"))
      (libsource (lib "Southwestern College") (part "CAP-NP-2"))
    )
    (comp (ref "C114")
      (value "100nF")
      (footprint "CAPC0402(1005)60_L")
      (description "Chip Capacitor, 100nF +/-20%, 25V, 0402, Thickness 0.6 mm")
      (fields (field (name "TOLERANCE") "10%") (field (name "Comment") "Capacitor 100nF +/-20% 25V 0402"))
      (libsource (lib "Southwestern College") (part "CAP-NP-2"))
    )
    (comp (ref "C115")
      (value "100nF")
      (footprint "CAPC0402(1005)60_L")
      (description "Chip Capacitor, 100nF +/-20%, 25V, 0402, Thickness 0.6 mm")
      (fields (field (name "TOLERANCE") "10%") (field (name "Comment") "Capacitor 100nF +/-20% 25V 0402"))
      (libsource (lib "Southwestern College") (part "CAP-NP-2"))
    )
    (comp (ref "C116")
      (value "100nF")
      (footprint "CAPC0402(1005)60_L")
      (description "Chip Capacitor, 100nF +/-20%, 25V, 0402, Thickness 0.6 mm")
      (fields (field (name "TOLERANCE") "10%") (field (name "Comment") "Capacitor 100nF +/-20% 25V 0402"))
      (libsource (lib "Southwestern College") (part "CAP-NP-2"))
    )
    (comp (ref "C117")
      (value "100nF")
      (footprint "CAPC0402(1005)60_L")
      (description "Chip Capacitor, 100nF +/-20%, 25V, 0402, Thickness 0.6 mm")
      (fields (field (name "TOLERANCE") "10%") (field (name "Comment") "Capacitor 100nF +/-20% 25V 0402"))
      (libsource (lib "Southwestern College") (part "CAP-NP-2"))
    )
    (comp (ref "C118")
      (value "100nF")
      (footprint "CAPC0402(1005)60_L")
      (description "Chip Capacitor, 100nF +/-20%, 25V, 0402, Thickness 0.6 mm")
      (fields (field (name "TOLERANCE") "10%") (field (name "Comment") "Capacitor 100nF +/-20% 25V 0402"))
      (libsource (lib "Southwestern College") (part "CAP-NP-2"))
    )
    (comp (ref "C119")
      (value "100nF")
      (footprint "CAPC0402(1005)60_L")
      (description "Chip Capacitor, 100nF +/-20%, 25V, 0402, Thickness 0.6 mm")
      (fields (field (name "TOLERANCE") "10%") (field (name "Comment") "Capacitor 100nF +/-20% 25V 0402"))
      (libsource (lib "Southwestern College") (part "CAP-NP-2"))
    )
    (comp (ref "C120")
      (value "100nF")
      (footprint "CAPC0402(1005)60_L")
      (description "Chip Capacitor, 100nF +/-20%, 25V, 0402, Thickness 0.6 mm")
      (fields (field (name "TOLERANCE") "10%") (field (name "Comment") "Capacitor 100nF +/-20% 25V 0402"))
      (libsource (lib "Southwestern College") (part "CAP-NP-2"))
    )
    (comp (ref "C121")
      (value "100nF")
      (footprint "CAPC0402(1005)60_L")
      (description "Chip Capacitor, 100nF +/-20%, 25V, 0402, Thickness 0.6 mm")
      (fields (field (name "TOLERANCE") "10%") (field (name "Comment") "Capacitor 100nF +/-20% 25V 0402"))
      (libsource (lib "Southwestern College") (part "CAP-NP-2"))
    )
    (comp (ref "C122")
      (value "100nF")
      (footprint "CAPC0402(1005)60_L")
      (description "Chip Capacitor, 100nF +/-20%, 25V, 0402, Thickness 0.6 mm")
      (fields (field (name "TOLERANCE") "10%") (field (name "Comment") "Capacitor 100nF +/-20% 25V 0402"))
      (libsource (lib "Southwestern College") (part "CAP-NP-2"))
    )
    (comp (ref "C123")
      (value "100nF")
      (footprint "CAPC0402(1005)60_L")
      (description "Chip Capacitor, 100nF +/-20%, 25V, 0402, Thickness 0.6 mm")
      (fields (field (name "TOLERANCE") "10%") (field (name "Comment") "Capacitor 100nF +/-20% 25V 0402"))
      (libsource (lib "Southwestern College") (part "CAP-NP-2"))
    )
    (comp (ref "C124")
      (value "100nF")
      (footprint "CAPC0402(1005)60_L")
      (description "Chip Capacitor, 100nF +/-20%, 25V, 0402, Thickness 0.6 mm")
      (fields (field (name "TOLERANCE") "10%") (field (name "Comment") "Capacitor 100nF +/-20% 25V 0402"))
      (libsource (lib "Southwestern College") (part "CAP-NP-2"))
    )
    (comp (ref "C125")
      (value "100nF")
      (footprint "CAPC0402(1005)60_L")
      (description "Chip Capacitor, 100nF +/-20%, 25V, 0402, Thickness 0.6 mm")
      (fields (field (name "TOLERANCE") "10%") (field (name "Comment") "Capacitor 100nF +/-20% 25V 0402"))
      (libsource (lib "Southwestern College") (part "CAP-NP-2"))
    )
    (comp (ref "C126")
      (value "100nF")
      (footprint "CAPC0402(1005)60_L")
      (description "Chip Capacitor, 100nF +/-20%, 25V, 0402, Thickness 0.6 mm")
      (fields (field (name "TOLERANCE") "10%") (field (name "Comment") "Capacitor 100nF +/-20% 25V 0402"))
      (libsource (lib "Southwestern College") (part "CAP-NP-2"))
    )
    (comp (ref "C127")
      (value "100nF")
      (footprint "CAPC0402(1005)60_L")
      (description "Chip Capacitor, 100nF +/-20%, 25V, 0402, Thickness 0.6 mm")
      (fields (field (name "TOLERANCE") "10%") (field (name "Comment") "Capacitor 100nF +/-20% 25V 0402"))
      (libsource (lib "Southwestern College") (part "CAP-NP-2"))
    )
    (comp (ref "C128")
      (value "100nF")
      (footprint "CAPC0402(1005)60_L")
      (description "Chip Capacitor, 100nF +/-20%, 25V, 0402, Thickness 0.6 mm")
      (fields (field (name "TOLERANCE") "10%") (field (name "Comment") "Capacitor 100nF +/-20% 25V 0402"))
      (libsource (lib "Southwestern College") (part "CAP-NP-2"))
    )
    (comp (ref "C129")
      (value "100nF")
      (footprint "CAPC0402(1005)60_L")
      (description "Chip Capacitor, 100nF +/-20%, 25V, 0402, Thickness 0.6 mm")
      (fields (field (name "TOLERANCE") "10%") (field (name "Comment") "Capacitor 100nF +/-20% 25V 0402"))
      (libsource (lib "Southwestern College") (part "CAP-NP-2"))
    )
    (comp (ref "C130")
      (value "100nF")
      (footprint "CAPC0402(1005)60_L")
      (description "Chip Capacitor, 100nF +/-20%, 25V, 0402, Thickness 0.6 mm")
      (fields (field (name "TOLERANCE") "10%") (field (name "Comment") "Capacitor 100nF +/-20% 25V 0402"))
      (libsource (lib "Southwestern College") (part "CAP-NP-2"))
    )
    (comp (ref "C131")
      (value "100nF")
      (footprint "CAPC0402(1005)60_L")
      (description "Chip Capacitor, 100nF +/-20%, 25V, 0402, Thickness 0.6 mm")
      (fields (field (name "TOLERANCE") "10%") (field (name "Comment") "Capacitor 100nF +/-20% 25V 0402"))
      (libsource (lib "Southwestern College") (part "CAP-NP-2"))
    )
    (comp (ref "C132")
      (value "100nF")
      (footprint "CAPC0402(1005)60_L")
      (description "Chip Capacitor, 100nF +/-20%, 25V, 0402, Thickness 0.6 mm")
      (fields (field (name "TOLERANCE") "10%") (field (name "Comment") "Capacitor 100nF +/-20% 25V 0402"))
      (libsource (lib "Southwestern College") (part "CAP-NP-2"))
    )
    (comp (ref "C133")
      (value "100nF")
      (footprint "CAPC0402(1005)60_L")
      (description "Chip Capacitor, 100nF +/-20%, 25V, 0402, Thickness 0.6 mm")
      (fields (field (name "TOLERANCE") "10%") (field (name "Comment") "Capacitor 100nF +/-20% 25V 0402"))
      (libsource (lib "Southwestern College") (part "CAP-NP-2"))
    )
    (comp (ref "C134")
      (value "100nF")
      (footprint "CAPC0402(1005)60_L")
      (description "Chip Capacitor, 100nF +/-20%, 25V, 0402, Thickness 0.6 mm")
      (fields (field (name "TOLERANCE") "10%") (field (name "Comment") "Capacitor 100nF +/-20% 25V 0402"))
      (libsource (lib "Southwestern College") (part "CAP-NP-2"))
    )
    (comp (ref "C135")
      (value "100nF")
      (footprint "CAPC0402(1005)60_L")
      (description "Chip Capacitor, 100nF +/-20%, 25V, 0402, Thickness 0.6 mm")
      (fields (field (name "TOLERANCE") "10%") (field (name "Comment") "Capacitor 100nF +/-20% 25V 0402"))
      (libsource (lib "Southwestern College") (part "CAP-NP-2"))
    )
    (comp (ref "C136")
      (value "100nF")
      (footprint "CAPC0402(1005)60_L")
      (description "Chip Capacitor, 100nF +/-20%, 25V, 0402, Thickness 0.6 mm")
      (fields (field (name "TOLERANCE") "10%") (field (name "Comment") "Capacitor 100nF +/-20% 25V 0402"))
      (libsource (lib "Southwestern College") (part "CAP-NP-2"))
    )
    (comp (ref "C137")
      (value "100nF")
      (footprint "CAPC0402(1005)60_L")
      (description "Chip Capacitor, 100nF +/-20%, 25V, 0402, Thickness 0.6 mm")
      (fields (field (name "TOLERANCE") "10%") (field (name "Comment") "Capacitor 100nF +/-20% 25V 0402"))
      (libsource (lib "Southwestern College") (part "CAP-NP-2"))
    )
    (comp (ref "C138")
      (value "100nF")
      (footprint "CAPC0402(1005)60_L")
      (description "Chip Capacitor, 100nF +/-20%, 25V, 0402, Thickness 0.6 mm")
      (fields (field (name "TOLERANCE") "10%") (field (name "Comment") "Capacitor 100nF +/-20% 25V 0402"))
      (libsource (lib "Southwestern College") (part "CAP-NP-2"))
    )
    (comp (ref "C139")
      (value "100nF")
      (footprint "CAPC0402(1005)60_L")
      (description "Chip Capacitor, 100nF +/-20%, 25V, 0402, Thickness 0.6 mm")
      (fields (field (name "TOLERANCE") "10%") (field (name "Comment") "Capacitor 100nF +/-20% 25V 0402"))
      (libsource (lib "Southwestern College") (part "CAP-NP-2"))
    )
    (comp (ref "C140")
      (value "100nF")
      (footprint "CAPC0402(1005)60_L")
      (description "Chip Capacitor, 100nF +/-20%, 25V, 0402, Thickness 0.6 mm")
      (fields (field (name "TOLERANCE") "10%") (field (name "Comment") "Capacitor 100nF +/-20% 25V 0402"))
      (libsource (lib "Southwestern College") (part "CAP-NP-2"))
    )
    (comp (ref "C141")
      (value "100nF")
      (footprint "CAPC0402(1005)60_L")
      (description "Chip Capacitor, 100nF +/-20%, 25V, 0402, Thickness 0.6 mm")
      (fields (field (name "TOLERANCE") "10%") (field (name "Comment") "Capacitor 100nF +/-20% 25V 0402"))
      (libsource (lib "Southwestern College") (part "CAP-NP-2"))
    )
    (comp (ref "C142")
      (value "100nF")
      (footprint "CAPC0402(1005)60_L")
      (description "Chip Capacitor, 100nF +/-20%, 25V, 0402, Thickness 0.6 mm")
      (fields (field (name "TOLERANCE") "10%") (field (name "Comment") "Capacitor 100nF +/-20% 25V 0402"))
      (libsource (lib "Southwestern College") (part "CAP-NP-2"))
    )
    (comp (ref "C143")
      (value "100nF")
      (footprint "CAPC0402(1005)60_L")
      (description "Chip Capacitor, 100nF +/-20%, 25V, 0402, Thickness 0.6 mm")
      (fields (field (name "TOLERANCE") "10%") (field (name "Comment") "Capacitor 100nF +/-20% 25V 0402"))
      (libsource (lib "Southwestern College") (part "CAP-NP-2"))
    )
    (comp (ref "C144")
      (value "100nF")
      (footprint "CAPC0402(1005)60_L")
      (description "Chip Capacitor, 100nF +/-20%, 25V, 0402, Thickness 0.6 mm")
      (fields (field (name "TOLERANCE") "10%") (field (name "Comment") "Capacitor 100nF +/-20% 25V 0402"))
      (libsource (lib "Southwestern College") (part "CAP-NP-2"))
    )
    (comp (ref "C145")
      (value "100nF")
      (footprint "CAPC0402(1005)60_L")
      (description "Chip Capacitor, 100nF +/-20%, 25V, 0402, Thickness 0.6 mm")
      (fields (field (name "TOLERANCE") "10%") (field (name "Comment") "Capacitor 100nF +/-20% 25V 0402"))
      (libsource (lib "Southwestern College") (part "CAP-NP-2"))
    )
    (comp (ref "C146")
      (value "100nF")
      (footprint "CAPC0402(1005)60_L")
      (description "Chip Capacitor, 100nF +/-20%, 25V, 0402, Thickness 0.6 mm")
      (fields (field (name "TOLERANCE") "10%") (field (name "Comment") "Capacitor 100nF +/-20% 25V 0402"))
      (libsource (lib "Southwestern College") (part "CAP-NP-2"))
    )
    (comp (ref "C147")
      (value "100nF")
      (footprint "CAPC0402(1005)60_L")
      (description "Chip Capacitor, 100nF +/-20%, 25V, 0402, Thickness 0.6 mm")
      (fields (field (name "TOLERANCE") "10%") (field (name "Comment") "Capacitor 100nF +/-20% 25V 0402"))
      (libsource (lib "Southwestern College") (part "CAP-NP-2"))
    )
    (comp (ref "C148")
      (value "100nF")
      (footprint "CAPC0402(1005)60_L")
      (description "Chip Capacitor, 100nF +/-20%, 25V, 0402, Thickness 0.6 mm")
      (fields (field (name "TOLERANCE") "10%") (field (name "Comment") "Capacitor 100nF +/-20% 25V 0402"))
      (libsource (lib "Southwestern College") (part "CAP-NP-2"))
    )
    (comp (ref "C149")
      (value "100nF")
      (footprint "CAPC0402(1005)60_L")
      (description "Chip Capacitor, 100nF +/-20%, 25V, 0402, Thickness 0.6 mm")
      (fields (field (name "TOLERANCE") "10%") (field (name "Comment") "Capacitor 100nF +/-20% 25V 0402"))
      (libsource (lib "Southwestern College") (part "CAP-NP-2"))
    )
    (comp (ref "C150")
      (value "100nF")
      (footprint "CAPC0402(1005)60_L")
      (description "Chip Capacitor, 100nF +/-20%, 25V, 0402, Thickness 0.6 mm")
      (fields (field (name "TOLERANCE") "10%") (field (name "Comment") "Capacitor 100nF +/-20% 25V 0402"))
      (libsource (lib "Southwestern College") (part "CAP-NP-2"))
    )
    (comp (ref "C151")
      (value "100nF")
      (footprint "CAPC0402(1005)60_L")
      (description "Chip Capacitor, 100nF +/-20%, 25V, 0402, Thickness 0.6 mm")
      (fields (field (name "TOLERANCE") "10%") (field (name "Comment") "Capacitor 100nF +/-20% 25V 0402"))
      (libsource (lib "Southwestern College") (part "CAP-NP-2"))
    )
    (comp (ref "C152")
      (value "100nF")
      (footprint "CAPC0402(1005)60_L")
      (description "Chip Capacitor, 100nF +/-20%, 25V, 0402, Thickness 0.6 mm")
      (fields (field (name "TOLERANCE") "10%") (field (name "Comment") "Capacitor 100nF +/-20% 25V 0402"))
      (libsource (lib "Southwestern College") (part "CAP-NP-2"))
    )
    (comp (ref "C153")
      (value "100nF")
      (footprint "CAPC0402(1005)60_L")
      (description "Chip Capacitor, 100nF +/-20%, 25V, 0402, Thickness 0.6 mm")
      (fields (field (name "TOLERANCE") "10%") (field (name "Comment") "Capacitor 100nF +/-20% 25V 0402"))
      (libsource (lib "Southwestern College") (part "CAP-NP-2"))
    )
    (comp (ref "C154")
      (value "100nF")
      (footprint "CAPC0402(1005)60_L")
      (description "Chip Capacitor, 100nF +/-20%, 25V, 0402, Thickness 0.6 mm")
      (fields (field (name "TOLERANCE") "10%") (field (name "Comment") "Capacitor 100nF +/-20% 25V 0402"))
      (libsource (lib "Southwestern College") (part "CAP-NP-2"))
    )
    (comp (ref "C155")
      (value "100nF")
      (footprint "CAPC0402(1005)60_L")
      (description "Chip Capacitor, 100nF +/-20%, 25V, 0402, Thickness 0.6 mm")
      (fields (field (name "TOLERANCE") "10%") (field (name "Comment") "Capacitor 100nF +/-20% 25V 0402"))
      (libsource (lib "Southwestern College") (part "CAP-NP-2"))
    )
    (comp (ref "C156")
      (value "100nF")
      (footprint "CAPC0402(1005)60_L")
      (description "Chip Capacitor, 100nF +/-20%, 25V, 0402, Thickness 0.6 mm")
      (fields (field (name "TOLERANCE") "10%") (field (name "Comment") "Capacitor 100nF +/-20% 25V 0402"))
      (libsource (lib "Southwestern College") (part "CAP-NP-2"))
    )
    (comp (ref "C157")
      (value "100nF")
      (footprint "CAPC0402(1005)60_L")
      (description "Chip Capacitor, 100nF +/-20%, 25V, 0402, Thickness 0.6 mm")
      (fields (field (name "TOLERANCE") "10%") (field (name "Comment") "Capacitor 100nF +/-20% 25V 0402"))
      (libsource (lib "Southwestern College") (part "CAP-NP-2"))
    )
    (comp (ref "C158")
      (value "100nF")
      (footprint "CAPC0402(1005)60_L")
      (description "Chip Capacitor, 100nF +/-20%, 25V, 0402, Thickness 0.6 mm")
      (fields (field (name "TOLERANCE") "10%") (field (name "Comment") "Capacitor 100nF +/-20% 25V 0402"))
      (libsource (lib "Southwestern College") (part "CAP-NP-2"))
    )
    (comp (ref "C159")
      (value "100nF")
      (footprint "CAPC0402(1005)60_L")
      (description "Chip Capacitor, 100nF +/-20%, 25V, 0402, Thickness 0.6 mm")
      (fields (field (name "TOLERANCE") "10%") (field (name "Comment") "Capacitor 100nF +/-20% 25V 0402"))
      (libsource (lib "Southwestern College") (part "CAP-NP-2"))
    )
    (comp (ref "U0")
      (value "WS2812B")
      (footprint "ADAI-WS2812B_V")
      (fields (field (name "MANUFACTURER") "Adafruit Industries"))
      (libsource (lib "Southwestern College") (part "ADAI-WS2812B-4"))
    )
    (comp (ref "U1")
      (value "WS2812B")
      (footprint "ADAI-WS2812B_V")
      (fields (field (name "MANUFACTURER") "Adafruit Industries"))
      (libsource (lib "Southwestern College") (part "ADAI-WS2812B-4"))
    )
    (comp (ref "U2")
      (value "WS2812B")
      (footprint "ADAI-WS2812B_V")
      (fields (field (name "MANUFACTURER") "Adafruit Industries"))
      (libsource (lib "Southwestern College") (part "ADAI-WS2812B-4"))
    )
    (comp (ref "U3")
      (value "WS2812B")
      (footprint "ADAI-WS2812B_V")
      (fields (field (name "MANUFACTURER") "Adafruit Industries"))
      (libsource (lib "Southwestern College") (part "ADAI-WS2812B-4"))
    )
    (comp (ref "U4")
      (value "WS2812B")
      (footprint "ADAI-WS2812B_V")
      (fields (field (name "MANUFACTURER") "Adafruit Industries"))
      (libsource (lib "Southwestern College") (part "ADAI-WS2812B-4"))
    )
    (comp (ref "U5")
      (value "WS2812B")
      (footprint "ADAI-WS2812B_V")
      (fields (field (name "MANUFACTURER") "Adafruit Industries"))
      (libsource (lib "Southwestern College") (part "ADAI-WS2812B-4"))
    )
    (comp (ref "U6")
      (value "WS2812B")
      (footprint "ADAI-WS2812B_V")
      (fields (field (name "MANUFACTURER") "Adafruit Industries"))
      (libsource (lib "Southwestern College") (part "ADAI-WS2812B-4"))
    )
    (comp (ref "U7")
      (value "WS2812B")
      (footprint "ADAI-WS2812B_V")
      (fields (field (name "MANUFACTURER") "Adafruit Industries"))
      (libsource (lib "Southwestern College") (part "ADAI-WS2812B-4"))
    )
    (comp (ref "U8")
      (value "WS2812B")
      (footprint "ADAI-WS2812B_V")
      (fields (field (name "MANUFACTURER") "Adafruit Industries"))
      (libsource (lib "Southwestern College") (part "ADAI-WS2812B-4"))
    )
    (comp (ref "U9")
      (value "WS2812B")
      (footprint "ADAI-WS2812B_V")
      (fields (field (name "MANUFACTURER") "Adafruit Industries"))
      (libsource (lib "Southwestern College") (part "ADAI-WS2812B-4"))
    )
    (comp (ref "U10")
      (value "WS2812B")
      (footprint "ADAI-WS2812B_V")
      (fields (field (name "MANUFACTURER") "Adafruit Industries"))
      (libsource (lib "Southwestern College") (part "ADAI-WS2812B-4"))
    )
    (comp (ref "U11")
      (value "WS2812B")
      (footprint "ADAI-WS2812B_V")
      (fields (field (name "MANUFACTURER") "Adafruit Industries"))
      (libsource (lib "Southwestern College") (part "ADAI-WS2812B-4"))
    )
    (comp (ref "U12")
      (value "WS2812B")
      (footprint "ADAI-WS2812B_V")
      (fields (field (name "MANUFACTURER") "Adafruit Industries"))
      (libsource (lib "Southwestern College") (part "ADAI-WS2812B-4"))
    )
    (comp (ref "U13")
      (value "WS2812B")
      (footprint "ADAI-WS2812B_V")
      (fields (field (name "MANUFACTURER") "Adafruit Industries"))
      (libsource (lib "Southwestern College") (part "ADAI-WS2812B-4"))
    )
    (comp (ref "U14")
      (value "WS2812B")
      (footprint "ADAI-WS2812B_V")
      (fields (field (name "MANUFACTURER") "Adafruit Industries"))
      (libsource (lib "Southwestern College") (part "ADAI-WS2812B-4"))
    )
    (comp (ref "U15")
      (value "WS2812B")
      (footprint "ADAI-WS2812B_V")
      (fields (field (name "MANUFACTURER") "Adafruit Industries"))
      (libsource (lib "Southwestern College") (part "ADAI-WS2812B-4"))
    )
    (comp (ref "U16")
      (value "WS2812B")
      (footprint "ADAI-WS2812B_V")
      (fields (field (name "MANUFACTURER") "Adafruit Industries"))
      (libsource (lib "Southwestern College") (part "ADAI-WS2812B-4"))
    )
    (comp (ref "U17")
      (value "WS2812B")
      (footprint "ADAI-WS2812B_V")
      (fields (field (name "MANUFACTURER") "Adafruit Industries"))
      (libsource (lib "Southwestern College") (part "ADAI-WS2812B-4"))
    )
    (comp (ref "U18")
      (value "WS2812B")
      (footprint "ADAI-WS2812B_V")
      (fields (field (name "MANUFACTURER") "Adafruit Industries"))
      (libsource (lib "Southwestern College") (part "ADAI-WS2812B-4"))
    )
    (comp (ref "U19")
      (value "WS2812B")
      (footprint "ADAI-WS2812B_V")
      (fields (field (name "MANUFACTURER") "Adafruit Industries"))
      (libsource (lib "Southwestern College") (part "ADAI-WS2812B-4"))
    )
    (comp (ref "U20")
      (value "WS2812B")
      (footprint "ADAI-WS2812B_V")
      (fields (field (name "MANUFACTURER") "Adafruit Industries"))
      (libsource (lib "Southwestern College") (part "ADAI-WS2812B-4"))
    )
    (comp (ref "U21")
      (value "WS2812B")
      (footprint "ADAI-WS2812B_V")
      (fields (field (name "MANUFACTURER") "Adafruit Industries"))
      (libsource (lib "Southwestern College") (part "ADAI-WS2812B-4"))
    )
    (comp (ref "U22")
      (value "WS2812B")
      (footprint "ADAI-WS2812B_V")
      (fields (field (name "MANUFACTURER") "Adafruit Industries"))
      (libsource (lib "Southwestern College") (part "ADAI-WS2812B-4"))
    )
    (comp (ref "U23")
      (value "WS2812B")
      (footprint "ADAI-WS2812B_V")
      (fields (field (name "MANUFACTURER") "Adafruit Industries"))
      (libsource (lib "Southwestern College") (part "ADAI-WS2812B-4"))
    )
    (comp (ref "U24")
      (value "WS2812B")
      (footprint "ADAI-WS2812B_V")
      (fields (field (name "MANUFACTURER") "Adafruit Industries"))
      (libsource (lib "Southwestern College") (part "ADAI-WS2812B-4"))
    )
    (comp (ref "U25")
      (value "WS2812B")
      (footprint "ADAI-WS2812B_V")
      (fields (field (name "MANUFACTURER") "Adafruit Industries"))
      (libsource (lib "Southwestern College") (part "ADAI-WS2812B-4"))
    )
    (comp (ref "U26")
      (value "WS2812B")
      (footprint "ADAI-WS2812B_V")
      (fields (field (name "MANUFACTURER") "Adafruit Industries"))
      (libsource (lib "Southwestern College") (part "ADAI-WS2812B-4"))
    )
    (comp (ref "U27")
      (value "WS2812B")
      (footprint "ADAI-WS2812B_V")
      (fields (field (name "MANUFACTURER") "Adafruit Industries"))
      (libsource (lib "Southwestern College") (part "ADAI-WS2812B-4"))
    )
    (comp (ref "U28")
      (value "WS2812B")
      (footprint "ADAI-WS2812B_V")
      (fields (field (name "MANUFACTURER") "Adafruit Industries"))
      (libsource (lib "Southwestern College") (part "ADAI-WS2812B-4"))
    )
    (comp (ref "U29")
      (value "WS2812B")
      (footprint "ADAI-WS2812B_V")
      (fields (field (name "MANUFACTURER") "Adafruit Industries"))
      (libsource (lib "Southwestern College") (part "ADAI-WS2812B-4"))
    )
    (comp (ref "U30")
      (value "WS2812B")
      (footprint "ADAI-WS2812B_V")
      (fields (field (name "MANUFACTURER") "Adafruit Industries"))
      (libsource (lib "Southwestern College") (part "ADAI-WS2812B-4"))
    )
    (comp (ref "U31")
      (value "WS2812B")
      (footprint "ADAI-WS2812B_V")
      (fields (field (name "MANUFACTURER") "Adafruit Industries"))
      (libsource (lib "Southwestern College") (part "ADAI-WS2812B-4"))
    )
    (comp (ref "U32")
      (value "WS2812B")
      (footprint "ADAI-WS2812B_V")
      (fields (field (name "MANUFACTURER") "Adafruit Industries"))
      (libsource (lib "Southwestern College") (part "ADAI-WS2812B-4"))
    )
    (comp (ref "U33")
      (value "WS2812B")
      (footprint "ADAI-WS2812B_V")
      (fields (field (name "MANUFACTURER") "Adafruit Industries"))
      (libsource (lib "Southwestern College") (part "ADAI-WS2812B-4"))
    )
    (comp (ref "U34")
      (value "WS2812B")
      (footprint "ADAI-WS2812B_V")
      (fields (field (name "MANUFACTURER") "Adafruit Industries"))
      (libsource (lib "Southwestern College") (part "ADAI-WS2812B-4"))
    )
    (comp (ref "U35")
      (value "WS2812B")
      (footprint "ADAI-WS2812B_V")
      (fields (field (name "MANUFACTURER") "Adafruit Industries"))
      (libsource (lib "Southwestern College") (part "ADAI-WS2812B-4"))
    )
    (comp (ref "U36")
      (value "WS2812B")
      (footprint "ADAI-WS2812B_V")
      (fields (field (name "MANUFACTURER") "Adafruit Industries"))
      (libsource (lib "Southwestern College") (part "ADAI-WS2812B-4"))
    )
    (comp (ref "U37")
      (value "WS2812B")
      (footprint "ADAI-WS2812B_V")
      (fields (field (name "MANUFACTURER") "Adafruit Industries"))
      (libsource (lib "Southwestern College") (part "ADAI-WS2812B-4"))
    )
    (comp (ref "U38")
      (value "WS2812B")
      (footprint "ADAI-WS2812B_V")
      (fields (field (name "MANUFACTURER") "Adafruit Industries"))
      (libsource (lib "Southwestern College") (part "ADAI-WS2812B-4"))
    )
    (comp (ref "U39")
      (value "WS2812B")
      (footprint "ADAI-WS2812B_V")
      (fields (field (name "MANUFACTURER") "Adafruit Industries"))
      (libsource (lib "Southwestern College") (part "ADAI-WS2812B-4"))
    )
    (comp (ref "U40")
      (value "WS2812B")
      (footprint "ADAI-WS2812B_V")
      (fields (field (name "MANUFACTURER") "Adafruit Industries"))
      (libsource (lib "Southwestern College") (part "ADAI-WS2812B-4"))
    )
    (comp (ref "U41")
      (value "WS2812B")
      (footprint "ADAI-WS2812B_V")
      (fields (field (name "MANUFACTURER") "Adafruit Industries"))
      (libsource (lib "Southwestern College") (part "ADAI-WS2812B-4"))
    )
    (comp (ref "U42")
      (value "WS2812B")
      (footprint "ADAI-WS2812B_V")
      (fields (field (name "MANUFACTURER") "Adafruit Industries"))
      (libsource (lib "Southwestern College") (part "ADAI-WS2812B-4"))
    )
    (comp (ref "U43")
      (value "WS2812B")
      (footprint "ADAI-WS2812B_V")
      (fields (field (name "MANUFACTURER") "Adafruit Industries"))
      (libsource (lib "Southwestern College") (part "ADAI-WS2812B-4"))
    )
    (comp (ref "U44")
      (value "WS2812B")
      (footprint "ADAI-WS2812B_V")
      (fields (field (name "MANUFACTURER") "Adafruit Industries"))
      (libsource (lib "Southwestern College") (part "ADAI-WS2812B-4"))
    )
    (comp (ref "U45")
      (value "WS2812B")
      (footprint "ADAI-WS2812B_V")
      (fields (field (name "MANUFACTURER") "Adafruit Industries"))
      (libsource (lib "Southwestern College") (part "ADAI-WS2812B-4"))
    )
    (comp (ref "U46")
      (value "WS2812B")
      (footprint "ADAI-WS2812B_V")
      (fields (field (name "MANUFACTURER") "Adafruit Industries"))
      (libsource (lib "Southwestern College") (part "ADAI-WS2812B-4"))
    )
    (comp (ref "U47")
      (value "WS2812B")
      (footprint "ADAI-WS2812B_V")
      (fields (field (name "MANUFACTURER") "Adafruit Industries"))
      (libsource (lib "Southwestern College") (part "ADAI-WS2812B-4"))
    )
    (comp (ref "U48")
      (value "WS2812B")
      (footprint "ADAI-WS2812B_V")
      (fields (field (name "MANUFACTURER") "Adafruit Industries"))
      (libsource (lib "Southwestern College") (part "ADAI-WS2812B-4"))
    )
    (comp (ref "U49")
      (value "WS2812B")
      (footprint "ADAI-WS2812B_V")
      (fields (field (name "MANUFACTURER") "Adafruit Industries"))
      (libsource (lib "Southwestern College") (part "ADAI-WS2812B-4"))
    )
    (comp (ref "U50")
      (value "WS2812B")
      (footprint "ADAI-WS2812B_V")
      (fields (field (name "MANUFACTURER") "Adafruit Industries"))
      (libsource (lib "Southwestern College") (part "ADAI-WS2812B-4"))
    )
    (comp (ref "U51")
      (value "WS2812B")
      (footprint "ADAI-WS2812B_V")
      (fields (field (name "MANUFACTURER") "Adafruit Industries"))
      (libsource (lib "Southwestern College") (part "ADAI-WS2812B-4"))
    )
    (comp (ref "U52")
      (value "WS2812B")
      (footprint "ADAI-WS2812B_V")
      (fields (field (name "MANUFACTURER") "Adafruit Industries"))
      (libsource (lib "Southwestern College") (part "ADAI-WS2812B-4"))
    )
    (comp (ref "U53")
      (value "WS2812B")
      (footprint "ADAI-WS2812B_V")
      (fields (field (name "MANUFACTURER") "Adafruit Industries"))
      (libsource (lib "Southwestern College") (part "ADAI-WS2812B-4"))
    )
    (comp (ref "U54")
      (value "WS2812B")
      (footprint "ADAI-WS2812B_V")
      (fields (field (name "MANUFACTURER") "Adafruit Industries"))
      (libsource (lib "Southwestern College") (part "ADAI-WS2812B-4"))
    )
    (comp (ref "U55")
      (value "WS2812B")
      (footprint "ADAI-WS2812B_V")
      (fields (field (name "MANUFACTURER") "Adafruit Industries"))
      (libsource (lib "Southwestern College") (part "ADAI-WS2812B-4"))
    )
    (comp (ref "U56")
      (value "WS2812B")
      (footprint "ADAI-WS2812B_V")
      (fields (field (name "MANUFACTURER") "Adafruit Industries"))
      (libsource (lib "Southwestern College") (part "ADAI-WS2812B-4"))
    )
    (comp (ref "U57")
      (value "WS2812B")
      (footprint "ADAI-WS2812B_V")
      (fields (field (name "MANUFACTURER") "Adafruit Industries"))
      (libsource (lib "Southwestern College") (part "ADAI-WS2812B-4"))
    )
    (comp (ref "U58")
      (value "WS2812B")
      (footprint "ADAI-WS2812B_V")
      (fields (field (name "MANUFACTURER") "Adafruit Industries"))
      (libsource (lib "Southwestern College") (part "ADAI-WS2812B-4"))
    )
    (comp (ref "U59")
      (value "WS2812B")
      (footprint "ADAI-WS2812B_V")
      (fields (field (name "MANUFACTURER") "Adafruit Industries"))
      (libsource (lib "Southwestern College") (part "ADAI-WS2812B-4"))
    )
    (comp (ref "U60")
      (value "WS2812B")
      (footprint "ADAI-WS2812B_V")
      (fields (field (name "MANUFACTURER") "Adafruit Industries"))
      (libsource (lib "Southwestern College") (part "ADAI-WS2812B-4"))
    )
    (comp (ref "U61")
      (value "WS2812B")
      (footprint "ADAI-WS2812B_V")
      (fields (field (name "MANUFACTURER") "Adafruit Industries"))
      (libsource (lib "Southwestern College") (part "ADAI-WS2812B-4"))
    )
    (comp (ref "U62")
      (value "WS2812B")
      (footprint "ADAI-WS2812B_V")
      (fields (field (name "MANUFACTURER") "Adafruit Industries"))
      (libsource (lib "Southwestern College") (part "ADAI-WS2812B-4"))
    )
    (comp (ref "U63")
      (value "WS2812B")
      (footprint "ADAI-WS2812B_V")
      (fields (field (name "MANUFACTURER") "Adafruit Industries"))
      (libsource (lib "Southwestern College") (part "ADAI-WS2812B-4"))
    )
    (comp (ref "U64")
      (value "WS2812B")
      (footprint "ADAI-WS2812B_V")
      (fields (field (name "MANUFACTURER") "Adafruit Industries"))
      (libsource (lib "Southwestern College") (part "ADAI-WS2812B-4"))
    )
    (comp (ref "U65")
      (value "WS2812B")
      (footprint "ADAI-WS2812B_V")
      (fields (field (name "MANUFACTURER") "Adafruit Industries"))
      (libsource (lib "Southwestern College") (part "ADAI-WS2812B-4"))
    )
    (comp (ref "U66")
      (value "WS2812B")
      (footprint "ADAI-WS2812B_V")
      (fields (field (name "MANUFACTURER") "Adafruit Industries"))
      (libsource (lib "Southwestern College") (part "ADAI-WS2812B-4"))
    )
    (comp (ref "U67")
      (value "WS2812B")
      (footprint "ADAI-WS2812B_V")
      (fields (field (name "MANUFACTURER") "Adafruit Industries"))
      (libsource (lib "Southwestern College") (part "ADAI-WS2812B-4"))
    )
    (comp (ref "U68")
      (value "WS2812B")
      (footprint "ADAI-WS2812B_V")
      (fields (field (name "MANUFACTURER") "Adafruit Industries"))
      (libsource (lib "Southwestern College") (part "ADAI-WS2812B-4"))
    )
    (comp (ref "U69")
      (value "WS2812B")
      (footprint "ADAI-WS2812B_V")
      (fields (field (name "MANUFACTURER") "Adafruit Industries"))
      (libsource (lib "Southwestern College") (part "ADAI-WS2812B-4"))
    )
    (comp (ref "U70")
      (value "WS2812B")
      (footprint "ADAI-WS2812B_V")
      (fields (field (name "MANUFACTURER") "Adafruit Industries"))
      (libsource (lib "Southwestern College") (part "ADAI-WS2812B-4"))
    )
    (comp (ref "U71")
      (value "WS2812B")
      (footprint "ADAI-WS2812B_V")
      (fields (field (name "MANUFACTURER") "Adafruit Industries"))
      (libsource (lib "Southwestern College") (part "ADAI-WS2812B-4"))
    )
    (comp (ref "U72")
      (value "WS2812B")
      (footprint "ADAI-WS2812B_V")
      (fields (field (name "MANUFACTURER") "Adafruit Industries"))
      (libsource (lib "Southwestern College") (part "ADAI-WS2812B-4"))
    )
    (comp (ref "U73")
      (value "WS2812B")
      (footprint "ADAI-WS2812B_V")
      (fields (field (name "MANUFACTURER") "Adafruit Industries"))
      (libsource (lib "Southwestern College") (part "ADAI-WS2812B-4"))
    )
    (comp (ref "U74")
      (value "WS2812B")
      (footprint "ADAI-WS2812B_V")
      (fields (field (name "MANUFACTURER") "Adafruit Industries"))
      (libsource (lib "Southwestern College") (part "ADAI-WS2812B-4"))
    )
    (comp (ref "U75")
      (value "WS2812B")
      (footprint "ADAI-WS2812B_V")
      (fields (field (name "MANUFACTURER") "Adafruit Industries"))
      (libsource (lib "Southwestern College") (part "ADAI-WS2812B-4"))
    )
    (comp (ref "U76")
      (value "WS2812B")
      (footprint "ADAI-WS2812B_V")
      (fields (field (name "MANUFACTURER") "Adafruit Industries"))
      (libsource (lib "Southwestern College") (part "ADAI-WS2812B-4"))
    )
    (comp (ref "U77")
      (value "WS2812B")
      (footprint "ADAI-WS2812B_V")
      (fields (field (name "MANUFACTURER") "Adafruit Industries"))
      (libsource (lib "Southwestern College") (part "ADAI-WS2812B-4"))
    )
    (comp (ref "U78")
      (value "WS2812B")
      (footprint "ADAI-WS2812B_V")
      (fields (field (name "MANUFACTURER") "Adafruit Industries"))
      (libsource (lib "Southwestern College") (part "ADAI-WS2812B-4"))
    )
    (comp (ref "U79")
      (value "WS2812B")
      (footprint "ADAI-WS2812B_V")
      (fields (field (name "MANUFACTURER") "Adafruit Industries"))
      (libsource (lib "Southwestern College") (part "ADAI-WS2812B-4"))
    )
    (comp (ref "U80")
      (value "WS2812B")
      (footprint "ADAI-WS2812B_V")
      (fields (field (name "MANUFACTURER") "Adafruit Industries"))
      (libsource (lib "Southwestern College") (part "ADAI-WS2812B-4"))
    )
    (comp (ref "U81")
      (value "WS2812B")
      (footprint "ADAI-WS2812B_V")
      (fields (field (name "MANUFACTURER") "Adafruit Industries"))
      (libsource (lib "Southwestern College") (part "ADAI-WS2812B-4"))
    )
    (comp (ref "U82")
      (value "WS2812B")
      (footprint "ADAI-WS2812B_V")
      (fields (field (name "MANUFACTURER") "Adafruit Industries"))
      (libsource (lib "Southwestern College") (part "ADAI-WS2812B-4"))
    )
    (comp (ref "U83")
      (value "WS2812B")
      (footprint "ADAI-WS2812B_V")
      (fields (field (name "MANUFACTURER") "Adafruit Industries"))
      (libsource (lib "Southwestern College") (part "ADAI-WS2812B-4"))
    )
    (comp (ref "U84")
      (value "WS2812B")
      (footprint "ADAI-WS2812B_V")
      (fields (field (name "MANUFACTURER") "Adafruit Industries"))
      (libsource (lib "Southwestern College") (part "ADAI-WS2812B-4"))
    )
    (comp (ref "U85")
      (value "WS2812B")
      (footprint "ADAI-WS2812B_V")
      (fields (field (name "MANUFACTURER") "Adafruit Industries"))
      (libsource (lib "Southwestern College") (part "ADAI-WS2812B-4"))
    )
    (comp (ref "U86")
      (value "WS2812B")
      (footprint "ADAI-WS2812B_V")
      (fields (field (name "MANUFACTURER") "Adafruit Industries"))
      (libsource (lib "Southwestern College") (part "ADAI-WS2812B-4"))
    )
    (comp (ref "U87")
      (value "WS2812B")
      (footprint "ADAI-WS2812B_V")
      (fields (field (name "MANUFACTURER") "Adafruit Industries"))
      (libsource (lib "Southwestern College") (part "ADAI-WS2812B-4"))
    )
    (comp (ref "U88")
      (value "WS2812B")
      (footprint "ADAI-WS2812B_V")
      (fields (field (name "MANUFACTURER") "Adafruit Industries"))
      (libsource (lib "Southwestern College") (part "ADAI-WS2812B-4"))
    )
    (comp (ref "U89")
      (value "WS2812B")
      (footprint "ADAI-WS2812B_V")
      (fields (field (name "MANUFACTURER") "Adafruit Industries"))
      (libsource (lib "Southwestern College") (part "ADAI-WS2812B-4"))
    )
    (comp (ref "U90")
      (value "WS2812B")
      (footprint "ADAI-WS2812B_V")
      (fields (field (name "MANUFACTURER") "Adafruit Industries"))
      (libsource (lib "Southwestern College") (part "ADAI-WS2812B-4"))
    )
    (comp (ref "U91")
      (value "WS2812B")
      (footprint "ADAI-WS2812B_V")
      (fields (field (name "MANUFACTURER") "Adafruit Industries"))
      (libsource (lib "Southwestern College") (part "ADAI-WS2812B-4"))
    )
    (comp (ref "U92")
      (value "WS2812B")
      (footprint "ADAI-WS2812B_V")
      (fields (field (name "MANUFACTURER") "Adafruit Industries"))
      (libsource (lib "Southwestern College") (part "ADAI-WS2812B-4"))
    )
    (comp (ref "U93")
      (value "WS2812B")
      (footprint "ADAI-WS2812B_V")
      (fields (field (name "MANUFACTURER") "Adafruit Industries"))
      (libsource (lib "Southwestern College") (part "ADAI-WS2812B-4"))
    )
    (comp (ref "U94")
      (value "WS2812B")
      (footprint "ADAI-WS2812B_V")
      (fields (field (name "MANUFACTURER") "Adafruit Industries"))
      (libsource (lib "Southwestern College") (part "ADAI-WS2812B-4"))
    )
    (comp (ref "U95")
      (value "WS2812B")
      (footprint "ADAI-WS2812B_V")
      (fields (field (name "MANUFACTURER") "Adafruit Industries"))
      (libsource (lib "Southwestern College") (part "ADAI-WS2812B-4"))
    )
    (comp (ref "U96")
      (value "WS2812B")
      (footprint "ADAI-WS2812B_V")
      (fields (field (name "MANUFACTURER") "Adafruit Industries"))
      (libsource (lib "Southwestern College") (part "ADAI-WS2812B-4"))
    )
    (comp (ref "U97")
      (value "WS2812B")
      (footprint "ADAI-WS2812B_V")
      (fields (field (name "MANUFACTURER") "Adafruit Industries"))
      (libsource (lib "Southwestern College") (part "ADAI-WS2812B-4"))
    )
    (comp (ref "U98")
      (value "WS2812B")
      (footprint "ADAI-WS2812B_V")
      (fields (field (name "MANUFACTURER") "Adafruit Industries"))
      (libsource (lib "Southwestern College") (part "ADAI-WS2812B-4"))
    )
    (comp (ref "U99")
      (value "WS2812B")
      (footprint "ADAI-WS2812B_V")
      (fields (field (name "MANUFACTURER") "Adafruit Industries"))
      (libsource (lib "Southwestern College") (part "ADAI-WS2812B-4"))
    )
    (comp (ref "U100")
      (value "WS2812B")
      (footprint "ADAI-WS2812B_V")
      (fields (field (name "MANUFACTURER") "Adafruit Industries"))
      (libsource (lib "Southwestern College") (part "ADAI-WS2812B-4"))
    )
    (comp (ref "U101")
      (value "WS2812B")
      (footprint "ADAI-WS2812B_V")
      (fields (field (name "MANUFACTURER") "Adafruit Industries"))
      (libsource (lib "Southwestern College") (part "ADAI-WS2812B-4"))
    )
    (comp (ref "U102")
      (value "WS2812B")
      (footprint "ADAI-WS2812B_V")
      (fields (field (name "MANUFACTURER") "Adafruit Industries"))
      (libsource (lib "Southwestern College") (part "ADAI-WS2812B-4"))
    )
    (comp (ref "U103")
      (value "WS2812B")
      (footprint "ADAI-WS2812B_V")
      (fields (field (name "MANUFACTURER") "Adafruit Industries"))
      (libsource (lib "Southwestern College") (part "ADAI-WS2812B-4"))
    )
    (comp (ref "U104")
      (value "WS2812B")
      (footprint "ADAI-WS2812B_V")
      (fields (field (name "MANUFACTURER") "Adafruit Industries"))
      (libsource (lib "Southwestern College") (part "ADAI-WS2812B-4"))
    )
    (comp (ref "U105")
      (value "WS2812B")
      (footprint "ADAI-WS2812B_V")
      (fields (field (name "MANUFACTURER") "Adafruit Industries"))
      (libsource (lib "Southwestern College") (part "ADAI-WS2812B-4"))
    )
    (comp (ref "U106")
      (value "WS2812B")
      (footprint "ADAI-WS2812B_V")
      (fields (field (name "MANUFACTURER") "Adafruit Industries"))
      (libsource (lib "Southwestern College") (part "ADAI-WS2812B-4"))
    )
    (comp (ref "U107")
      (value "WS2812B")
      (footprint "ADAI-WS2812B_V")
      (fields (field (name "MANUFACTURER") "Adafruit Industries"))
      (libsource (lib "Southwestern College") (part "ADAI-WS2812B-4"))
    )
    (comp (ref "U108")
      (value "WS2812B")
      (footprint "ADAI-WS2812B_V")
      (fields (field (name "MANUFACTURER") "Adafruit Industries"))
      (libsource (lib "Southwestern College") (part "ADAI-WS2812B-4"))
    )
    (comp (ref "U109")
      (value "WS2812B")
      (footprint "ADAI-WS2812B_V")
      (fields (field (name "MANUFACTURER") "Adafruit Industries"))
      (libsource (lib "Southwestern College") (part "ADAI-WS2812B-4"))
    )
    (comp (ref "U110")
      (value "WS2812B")
      (footprint "ADAI-WS2812B_V")
      (fields (field (name "MANUFACTURER") "Adafruit Industries"))
      (libsource (lib "Southwestern College") (part "ADAI-WS2812B-4"))
    )
    (comp (ref "U111")
      (value "WS2812B")
      (footprint "ADAI-WS2812B_V")
      (fields (field (name "MANUFACTURER") "Adafruit Industries"))
      (libsource (lib "Southwestern College") (part "ADAI-WS2812B-4"))
    )
    (comp (ref "U112")
      (value "WS2812B")
      (footprint "ADAI-WS2812B_V")
      (fields (field (name "MANUFACTURER") "Adafruit Industries"))
      (libsource (lib "Southwestern College") (part "ADAI-WS2812B-4"))
    )
    (comp (ref "U113")
      (value "WS2812B")
      (footprint "ADAI-WS2812B_V")
      (fields (field (name "MANUFACTURER") "Adafruit Industries"))
      (libsource (lib "Southwestern College") (part "ADAI-WS2812B-4"))
    )
    (comp (ref "U114")
      (value "WS2812B")
      (footprint "ADAI-WS2812B_V")
      (fields (field (name "MANUFACTURER") "Adafruit Industries"))
      (libsource (lib "Southwestern College") (part "ADAI-WS2812B-4"))
    )
    (comp (ref "U115")
      (value "WS2812B")
      (footprint "ADAI-WS2812B_V")
      (fields (field (name "MANUFACTURER") "Adafruit Industries"))
      (libsource (lib "Southwestern College") (part "ADAI-WS2812B-4"))
    )
    (comp (ref "U116")
      (value "WS2812B")
      (footprint "ADAI-WS2812B_V")
      (fields (field (name "MANUFACTURER") "Adafruit Industries"))
      (libsource (lib "Southwestern College") (part "ADAI-WS2812B-4"))
    )
    (comp (ref "U117")
      (value "WS2812B")
      (footprint "ADAI-WS2812B_V")
      (fields (field (name "MANUFACTURER") "Adafruit Industries"))
      (libsource (lib "Southwestern College") (part "ADAI-WS2812B-4"))
    )
    (comp (ref "U118")
      (value "WS2812B")
      (footprint "ADAI-WS2812B_V")
      (fields (field (name "MANUFACTURER") "Adafruit Industries"))
      (libsource (lib "Southwestern College") (part "ADAI-WS2812B-4"))
    )
    (comp (ref "U119")
      (value "WS2812B")
      (footprint "ADAI-WS2812B_V")
      (fields (field (name "MANUFACTURER") "Adafruit Industries"))
      (libsource (lib "Southwestern College") (part "ADAI-WS2812B-4"))
    )
    (comp (ref "U120")
      (value "WS2812B")
      (footprint "ADAI-WS2812B_V")
      (fields (field (name "MANUFACTURER") "Adafruit Industries"))
      (libsource (lib "Southwestern College") (part "ADAI-WS2812B-4"))
    )
    (comp (ref "U121")
      (value "WS2812B")
      (footprint "ADAI-WS2812B_V")
      (fields (field (name "MANUFACTURER") "Adafruit Industries"))
      (libsource (lib "Southwestern College") (part "ADAI-WS2812B-4"))
    )
    (comp (ref "U122")
      (value "WS2812B")
      (footprint "ADAI-WS2812B_V")
      (fields (field (name "MANUFACTURER") "Adafruit Industries"))
      (libsource (lib "Southwestern College") (part "ADAI-WS2812B-4"))
    )
    (comp (ref "U123")
      (value "WS2812B")
      (footprint "ADAI-WS2812B_V")
      (fields (field (name "MANUFACTURER") "Adafruit Industries"))
      (libsource (lib "Southwestern College") (part "ADAI-WS2812B-4"))
    )
    (comp (ref "U124")
      (value "WS2812B")
      (footprint "ADAI-WS2812B_V")
      (fields (field (name "MANUFACTURER") "Adafruit Industries"))
      (libsource (lib "Southwestern College") (part "ADAI-WS2812B-4"))
    )
    (comp (ref "U125")
      (value "WS2812B")
      (footprint "ADAI-WS2812B_V")
      (fields (field (name "MANUFACTURER") "Adafruit Industries"))
      (libsource (lib "Southwestern College") (part "ADAI-WS2812B-4"))
    )
    (comp (ref "U126")
      (value "WS2812B")
      (footprint "ADAI-WS2812B_V")
      (fields (field (name "MANUFACTURER") "Adafruit Industries"))
      (libsource (lib "Southwestern College") (part "ADAI-WS2812B-4"))
    )
    (comp (ref "U127")
      (value "WS2812B")
      (footprint "ADAI-WS2812B_V")
      (fields (field (name "MANUFACTURER") "Adafruit Industries"))
      (libsource (lib "Southwestern College") (part "ADAI-WS2812B-4"))
    )
    (comp (ref "U128")
      (value "WS2812B")
      (footprint "ADAI-WS2812B_V")
      (fields (field (name "MANUFACTURER") "Adafruit Industries"))
      (libsource (lib "Southwestern College") (part "ADAI-WS2812B-4"))
    )
    (comp (ref "U129")
      (value "WS2812B")
      (footprint "ADAI-WS2812B_V")
      (fields (field (name "MANUFACTURER") "Adafruit Industries"))
      (libsource (lib "Southwestern College") (part "ADAI-WS2812B-4"))
    )
    (comp (ref "U130")
      (value "WS2812B")
      (footprint "ADAI-WS2812B_V")
      (fields (field (name "MANUFACTURER") "Adafruit Industries"))
      (libsource (lib "Southwestern College") (part "ADAI-WS2812B-4"))
    )
    (comp (ref "U131")
      (value "WS2812B")
      (footprint "ADAI-WS2812B_V")
      (fields (field (name "MANUFACTURER") "Adafruit Industries"))
      (libsource (lib "Southwestern College") (part "ADAI-WS2812B-4"))
    )
    (comp (ref "U132")
      (value "WS2812B")
      (footprint "ADAI-WS2812B_V")
      (fields (field (name "MANUFACTURER") "Adafruit Industries"))
      (libsource (lib "Southwestern College") (part "ADAI-WS2812B-4"))
    )
    (comp (ref "U133")
      (value "WS2812B")
      (footprint "ADAI-WS2812B_V")
      (fields (field (name "MANUFACTURER") "Adafruit Industries"))
      (libsource (lib "Southwestern College") (part "ADAI-WS2812B-4"))
    )
    (comp (ref "U134")
      (value "WS2812B")
      (footprint "ADAI-WS2812B_V")
      (fields (field (name "MANUFACTURER") "Adafruit Industries"))
      (libsource (lib "Southwestern College") (part "ADAI-WS2812B-4"))
    )
    (comp (ref "U135")
      (value "WS2812B")
      (footprint "ADAI-WS2812B_V")
      (fields (field (name "MANUFACTURER") "Adafruit Industries"))
      (libsource (lib "Southwestern College") (part "ADAI-WS2812B-4"))
    )
    (comp (ref "U136")
      (value "WS2812B")
      (footprint "ADAI-WS2812B_V")
      (fields (field (name "MANUFACTURER") "Adafruit Industries"))
      (libsource (lib "Southwestern College") (part "ADAI-WS2812B-4"))
    )
    (comp (ref "U137")
      (value "WS2812B")
      (footprint "ADAI-WS2812B_V")
      (fields (field (name "MANUFACTURER") "Adafruit Industries"))
      (libsource (lib "Southwestern College") (part "ADAI-WS2812B-4"))
    )
    (comp (ref "U138")
      (value "WS2812B")
      (footprint "ADAI-WS2812B_V")
      (fields (field (name "MANUFACTURER") "Adafruit Industries"))
      (libsource (lib "Southwestern College") (part "ADAI-WS2812B-4"))
    )
    (comp (ref "U139")
      (value "WS2812B")
      (footprint "ADAI-WS2812B_V")
      (fields (field (name "MANUFACTURER") "Adafruit Industries"))
      (libsource (lib "Southwestern College") (part "ADAI-WS2812B-4"))
    )
    (comp (ref "U140")
      (value "WS2812B")
      (footprint "ADAI-WS2812B_V")
      (fields (field (name "MANUFACTURER") "Adafruit Industries"))
      (libsource (lib "Southwestern College") (part "ADAI-WS2812B-4"))
    )
    (comp (ref "U141")
      (value "WS2812B")
      (footprint "ADAI-WS2812B_V")
      (fields (field (name "MANUFACTURER") "Adafruit Industries"))
      (libsource (lib "Southwestern College") (part "ADAI-WS2812B-4"))
    )
  )
  (nets
    (net (code "1") (name "+5") (class "Default")
      (node (ref "C1") (pin "1") (pinfunction "1_1") (pintype "passive"))
      (node (ref "C100") (pin "1") (pinfunction "1_1") (pintype "passive"))
      (node (ref "C101") (pin "1") (pinfunction "1_1") (pintype "passive"))
      (node (ref "C102") (pin "1") (pinfunction "1_1") (pintype "passive"))
      (node (ref "C103") (pin "1") (pinfunction "1_1") (pintype "passive"))
      (node (ref "C104") (pin "1") (pinfunction "1_1") (pintype "passive"))
      (node (ref "C105") (pin "1") (pinfunction "1_1") (pintype "passive"))
      (node (ref "C106") (pin "1") (pinfunction "1_1") (pintype "passive"))
      (node (ref "C107") (pin "1") (pinfunction "1_1") (pintype "passive"))
      (node (ref "C108") (pin "1") (pinfunction "1_1") (pintype "passive"))
      (node (ref "C109") (pin "1") (pinfunction "1_1") (pintype "passive"))
      (node (ref "C110") (pin "1") (pinfunction "1_1") (pintype "passive"))
      (node (ref "C111") (pin "1") (pinfunction "1_1") (pintype "passive"))
      (node (ref "C112") (pin "1") (pinfunction "1_1") (pintype "passive"))
      (node (ref "C113") (pin "1") (pinfunction "1_1") (pintype "passive"))
      (node (ref "C114") (pin "1") (pinfunction "1_1") (pintype "passive"))
      (node (ref "C115") (pin "1") (pinfunction "1_1") (pintype "passive"))
      (node (ref "C116") (pin "1") (pinfunction "1_1") (pintype "passive"))
      (node (ref "C117") (pin "1") (pinfunction "1_1") (pintype "passive"))
      (node (ref "C118") (pin "1") (pinfunction "1_1") (pintype "passive"))
      (node (ref "C119") (pin "1") (pinfunction "1_1") (pintype "passive"))
      (node (ref "C120") (pin "1") (pinfunction "1_1") (pintype "passive"))
      (node (ref "C121") (pin "1") (pinfunction "1_1") (pintype "passive"))
      (node (ref "C122") (pin "1") (pinfunction "1_1") (pintype "passive"))
      (node (ref "C123") (pin "1") (pinfunction "1_1") (pintype "passive"))
      (node (ref "C124") (pin "1") (pinfunction "1_1") (pintype "passive"))
      (node (ref "C125") (pin "1") (pinfunction "1_1") (pintype "passive"))
      (node (ref "C126") (pin "1") (pinfunction "1_1") (pintype "passive"))
      (node (ref "C127") (pin "1") (pinfunction "1_1") (pintype "passive"))
      (node (ref "C128") (pin "1") (pinfunction "1_1") (pintype "passive"))
      (node (ref "C129") (pin "1") (pinfunction "1_1") (pintype "passive"))
      (node (ref "C130") (pin "1") (pinfunction "1_1") (pintype "passive"))
      (node (ref "C131") (pin "1") (pinfunction "1_1") (pintype "passive"))
      (node (ref "C132") (pin "1") (pinfunction "1_1") (pintype "passive"))
      (node (ref "C133") (pin "1") (pinfunction "1_1") (pintype "passive"))
      (node (ref "C134") (pin "1") (pinfunction "1_1") (pintype "passive"))
      (node (ref "C135") (pin "1") (pinfunction "1_1") (pintype "passive"))
      (node (ref "C136") (pin "1") (pinfunction "1_1") (pintype "passive"))
      (node (ref "C137") (pin "1") (pinfunction "1_1") (pintype "passive"))
      (node (ref "C138") (pin "1") (pinfunction "1_1") (pintype "passive"))
      (node (ref "C139") (pin "1") (pinfunction "1_1") (pintype "passive"))
      (node (ref "C140") (pin "1") (pinfunction "1_1") (pintype "passive"))
      (node (ref "C141") (pin "1") (pinfunction "1_1") (pintype "passive"))
      (node (ref "C142") (pin "1") (pinfunction "1_1") (pintype "passive"))
      (node (ref "C143") (pin "1") (pinfunction "1_1") (pintype "passive"))
      (node (ref "C144") (pin "1") (pinfunction "1_1") (pintype "passive"))
      (node (ref "C145") (pin "1") (pinfunction "1_1") (pintype "passive"))
      (node (ref "C146") (pin "1") (pinfunction "1_1") (pintype "passive"))
      (node (ref "C147") (pin "1") (pinfunction "1_1") (pintype "passive"))
      (node (ref "C148") (pin "1") (pinfunction "1_1") (pintype "passive"))
      (node (ref "C149") (pin "1") (pinfunction "1_1") (pintype "passive"))
      (node (ref "C150") (pin "1") (pinfunction "1_1") (pintype "passive"))
      (node (ref "C151") (pin "1") (pinfunction "1_1") (pintype "passive"))
      (node (ref "C152") (pin "1") (pinfunction "1_1") (pintype "passive"))
      (node (ref "C153") (pin "1") (pinfunction "1_1") (pintype "passive"))
      (node (ref "C154") (pin "1") (pinfunction "1_1") (pintype "passive"))
      (node (ref "C155") (pin "1") (pinfunction "1_1") (pintype "passive"))
      (node (ref "C156") (pin "1") (pinfunction "1_1") (pintype "passive"))
      (node (ref "C157") (pin "1") (pinfunction "1_1") (pintype "passive"))
      (node (ref "C158") (pin "1") (pinfunction "1_1") (pintype "passive"))
      (node (ref "C159") (pin "1") (pinfunction "1_1") (pintype "passive"))
      (node (ref "C2") (pin "1") (pinfunction "1_1") (pintype "passive"))
      (node (ref "C20") (pin "1") (pinfunction "1_1") (pintype "passive"))
      (node (ref "C21") (pin "1") (pinfunction "1_1") (pintype "passive"))
      (node (ref "C22") (pin "1") (pinfunction "1_1") (pintype "passive"))
      (node (ref "C23") (pin "1") (pinfunction "1_1") (pintype "passive"))
      (node (ref "C24") (pin "1") (pinfunction "1_1") (pintype "passive"))
      (node (ref "C25") (pin "1") (pinfunction "1_1") (pintype "passive"))
      (node (ref "C26") (pin "1") (pinfunction "1_1") (pintype "passive"))
      (node (ref "C27") (pin "1") (pinfunction "1_1") (pintype "passive"))
      (node (ref "C28") (pin "1") (pinfunction "1_1") (pintype "passive"))
      (node (ref "C29") (pin "1") (pinfunction "1_1") (pintype "passive"))
      (node (ref "C30") (pin "1") (pinfunction "1_1") (pintype "passive"))
      (node (ref "C31") (pin "1") (pinfunction "1_1") (pintype "passive"))
      (node (ref "C32") (pin "1") (pinfunction "1_1") (pintype "passive"))
      (node (ref "C33") (pin "1") (pinfunction "1_1") (pintype "passive"))
      (node (ref "C34") (pin "1") (pinfunction "1_1") (pintype "passive"))
      (node (ref "C35") (pin "1") (pinfunction "1_1") (pintype "passive"))
      (node (ref "C36") (pin "1") (pinfunction "1_1") (pintype "passive"))
      (node (ref "C37") (pin "1") (pinfunction "1_1") (pintype "passive"))
      (node (ref "C38") (pin "1") (pinfunction "1_1") (pintype "passive"))
      (node (ref "C39") (pin "1") (pinfunction "1_1") (pintype "passive"))
      (node (ref "C40") (pin "1") (pinfunction "1_1") (pintype "passive"))
      (node (ref "C41") (pin "1") (pinfunction "1_1") (pintype "passive"))
      (node (ref "C42") (pin "1") (pinfunction "1_1") (pintype "passive"))
      (node (ref "C43") (pin "1") (pinfunction "1_1") (pintype "passive"))
      (node (ref "C44") (pin "1") (pinfunction "1_1") (pintype "passive"))
      (node (ref "C45") (pin "1") (pinfunction "1_1") (pintype "passive"))
      (node (ref "C46") (pin "1") (pinfunction "1_1") (pintype "passive"))
      (node (ref "C47") (pin "1") (pinfunction "1_1") (pintype "passive"))
      (node (ref "C48") (pin "1") (pinfunction "1_1") (pintype "passive"))
      (node (ref "C49") (pin "1") (pinfunction "1_1") (pintype "passive"))
      (node (ref "C50") (pin "1") (pinfunction "1_1") (pintype "passive"))
      (node (ref "C51") (pin "1") (pinfunction "1_1") (pintype "passive"))
      (node (ref "C52") (pin "1") (pinfunction "1_1") (pintype "passive"))
      (node (ref "C53") (pin "1") (pinfunction "1_1") (pintype "passive"))
      (node (ref "C54") (pin "1") (pinfunction "1_1") (pintype "passive"))
      (node (ref "C55") (pin "1") (pinfunction "1_1") (pintype "passive"))
      (node (ref "C56") (pin "1") (pinfunction "1_1") (pintype "passive"))
      (node (ref "C57") (pin "1") (pinfunction "1_1") (pintype "passive"))
      (node (ref "C58") (pin "1") (pinfunction "1_1") (pintype "passive"))
      (node (ref "C59") (pin "1") (pinfunction "1_1") (pintype "passive"))
      (node (ref "C60") (pin "1") (pinfunction "1_1") (pintype "passive"))
      (node (ref "C61") (pin "1") (pinfunction "1_1") (pintype "passive"))
      (node (ref "C62") (pin "1") (pinfunction "1_1") (pintype "passive"))
      (node (ref "C63") (pin "1") (pinfunction "1_1") (pintype "passive"))
      (node (ref "C64") (pin "1") (pinfunction "1_1") (pintype "passive"))
      (node (ref "C65") (pin "1") (pinfunction "1_1") (pintype "passive"))
      (node (ref "C66") (pin "1") (pinfunction "1_1") (pintype "passive"))
      (node (ref "C67") (pin "1") (pinfunction "1_1") (pintype "passive"))
      (node (ref "C68") (pin "1") (pinfunction "1_1") (pintype "passive"))
      (node (ref "C69") (pin "1") (pinfunction "1_1") (pintype "passive"))
      (node (ref "C70") (pin "1") (pinfunction "1_1") (pintype "passive"))
      (node (ref "C71") (pin "1") (pinfunction "1_1") (pintype "passive"))
      (node (ref "C72") (pin "1") (pinfunction "1_1") (pintype "passive"))
      (node (ref "C73") (pin "1") (pinfunction "1_1") (pintype "passive"))
      (node (ref "C74") (pin "1") (pinfunction "1_1") (pintype "passive"))
      (node (ref "C75") (pin "1") (pinfunction "1_1") (pintype "passive"))
      (node (ref "C76") (pin "1") (pinfunction "1_1") (pintype "passive"))
      (node (ref "C77") (pin "1") (pinfunction "1_1") (pintype "passive"))
      (node (ref "C78") (pin "1") (pinfunction "1_1") (pintype "passive"))
      (node (ref "C79") (pin "1") (pinfunction "1_1") (pintype "passive"))
      (node (ref "C80") (pin "1") (pinfunction "1_1") (pintype "passive"))
      (node (ref "C81") (pin "1") (pinfunction "1_1") (pintype "passive"))
      (node (ref "C82") (pin "1") (pinfunction "1_1") (pintype "passive"))
      (node (ref "C83") (pin "1") (pinfunction "1_1") (pintype "passive"))
      (node (ref "C84") (pin "1") (pinfunction "1_1") (pintype "passive"))
      (node (ref "C85") (pin "1") (pinfunction "1_1") (pintype "passive"))
      (node (ref "C86") (pin "1") (pinfunction "1_1") (pintype "passive"))
      (node (ref "C87") (pin "1") (pinfunction "1_1") (pintype "passive"))
      (node (ref "C88") (pin "1") (pinfunction "1_1") (pintype "passive"))
      (node (ref "C89") (pin "1") (pinfunction "1_1") (pintype "passive"))
      (node (ref "C90") (pin "1") (pinfunction "1_1") (pintype "passive"))
      (node (ref "C91") (pin "1") (pinfunction "1_1") (pintype "passive"))
      (node (ref "C92") (pin "1") (pinfunction "1_1") (pintype "passive"))
      (node (ref "C93") (pin "1") (pinfunction "1_1") (pintype "passive"))
      (node (ref "C94") (pin "1") (pinfunction "1_1") (pintype "passive"))
      (node (ref "C95") (pin "1") (pinfunction "1_1") (pintype "passive"))
      (node (ref "C96") (pin "1") (pinfunction "1_1") (pintype "passive"))
      (node (ref "C97") (pin "1") (pinfunction "1_1") (pintype "passive"))
      (node (ref "C98") (pin "1") (pinfunction "1_1") (pintype "passive"))
      (node (ref "C99") (pin "1") (pinfunction "1_1") (pintype "passive"))
      (node (ref "U0") (pin "1") (pinfunction "VDD_1") (pintype "power_in"))
      (node (ref "U1") (pin "1") (pinfunction "VDD_1") (pintype "power_in"))
      (node (ref "U10") (pin "1") (pinfunction "VDD_1") (pintype "power_in"))
      (node (ref "U100") (pin "1") (pinfunction "VDD_1") (pintype "power_in"))
      (node (ref "U101") (pin "1") (pinfunction "VDD_1") (pintype "power_in"))
      (node (ref "U102") (pin "1") (pinfunction "VDD_1") (pintype "power_in"))
      (node (ref "U103") (pin "1") (pinfunction "VDD_1") (pintype "power_in"))
      (node (ref "U104") (pin "1") (pinfunction "VDD_1") (pintype "power_in"))
      (node (ref "U105") (pin "1") (pinfunction "VDD_1") (pintype "power_in"))
      (node (ref "U106") (pin "1") (pinfunction "VDD_1") (pintype "power_in"))
      (node (ref "U107") (pin "1") (pinfunction "VDD_1") (pintype "power_in"))
      (node (ref "U108") (pin "1") (pinfunction "VDD_1") (pintype "power_in"))
      (node (ref "U109") (pin "1") (pinfunction "VDD_1") (pintype "power_in"))
      (node (ref "U11") (pin "1") (pinfunction "VDD_1") (pintype "power_in"))
      (node (ref "U110") (pin "1") (pinfunction "VDD_1") (pintype "power_in"))
      (node (ref "U111") (pin "1") (pinfunction "VDD_1") (pintype "power_in"))
      (node (ref "U112") (pin "1") (pinfunction "VDD_1") (pintype "power_in"))
      (node (ref "U113") (pin "1") (pinfunction "VDD_1") (pintype "power_in"))
      (node (ref "U114") (pin "1") (pinfunction "VDD_1") (pintype "power_in"))
      (node (ref "U115") (pin "1") (pinfunction "VDD_1") (pintype "power_in"))
      (node (ref "U116") (pin "1") (pinfunction "VDD_1") (pintype "power_in"))
      (node (ref "U117") (pin "1") (pinfunction "VDD_1") (pintype "power_in"))
      (node (ref "U118") (pin "1") (pinfunction "VDD_1") (pintype "power_in"))
      (node (ref "U119") (pin "1") (pinfunction "VDD_1") (pintype "power_in"))
      (node (ref "U12") (pin "1") (pinfunction "VDD_1") (pintype "power_in"))
      (node (ref "U120") (pin "1") (pinfunction "VDD_1") (pintype "power_in"))
      (node (ref "U121") (pin "1") (pinfunction "VDD_1") (pintype "power_in"))
      (node (ref "U122") (pin "1") (pinfunction "VDD_1") (pintype "power_in"))
      (node (ref "U123") (pin "1") (pinfunction "VDD_1") (pintype "power_in"))
      (node (ref "U124") (pin "1") (pinfunction "VDD_1") (pintype "power_in"))
      (node (ref "U125") (pin "1") (pinfunction "VDD_1") (pintype "power_in"))
      (node (ref "U126") (pin "1") (pinfunction "VDD_1") (pintype "power_in"))
      (node (ref "U127") (pin "1") (pinfunction "VDD_1") (pintype "power_in"))
      (node (ref "U128") (pin "1") (pinfunction "VDD_1") (pintype "power_in"))
      (node (ref "U129") (pin "1") (pinfunction "VDD_1") (pintype "power_in"))
      (node (ref "U13") (pin "1") (pinfunction "VDD_1") (pintype "power_in"))
      (node (ref "U130") (pin "1") (pinfunction "VDD_1") (pintype "power_in"))
      (node (ref "U131") (pin "1") (pinfunction "VDD_1") (pintype "power_in"))
      (node (ref "U132") (pin "1") (pinfunction "VDD_1") (pintype "power_in"))
      (node (ref "U133") (pin "1") (pinfunction "VDD_1") (pintype "power_in"))
      (node (ref "U134") (pin "1") (pinfunction "VDD_1") (pintype "power_in"))
      (node (ref "U135") (pin "1") (pinfunction "VDD_1") (pintype "power_in"))
      (node (ref "U136") (pin "1") (pinfunction "VDD_1") (pintype "power_in"))
      (node (ref "U137") (pin "1") (pinfunction "VDD_1") (pintype "power_in"))
      (node (ref "U138") (pin "1") (pinfunction "VDD_1") (pintype "power_in"))
      (node (ref "U139") (pin "1") (pinfunction "VDD_1") (pintype "power_in"))
      (node (ref "U14") (pin "1") (pinfunction "VDD_1") (pintype "power_in"))
      (node (ref "U140") (pin "1") (pinfunction "VDD_1") (pintype "power_in"))
      (node (ref "U141") (pin "1") (pinfunction "VDD_1") (pintype "power_in"))
      (node (ref "U15") (pin "1") (pinfunction "VDD_1") (pintype "power_in"))
      (node (ref "U16") (pin "1") (pinfunction "VDD_1") (pintype "power_in"))
      (node (ref "U17") (pin "1") (pinfunction "VDD_1") (pintype "power_in"))
      (node (ref "U18") (pin "1") (pinfunction "VDD_1") (pintype "power_in"))
      (node (ref "U19") (pin "1") (pinfunction "VDD_1") (pintype "power_in"))
      (node (ref "U2") (pin "1") (pinfunction "VDD_1") (pintype "power_in"))
      (node (ref "U20") (pin "1") (pinfunction "VDD_1") (pintype "power_in"))
      (node (ref "U21") (pin "1") (pinfunction "VDD_1") (pintype "power_in"))
      (node (ref "U22") (pin "1") (pinfunction "VDD_1") (pintype "power_in"))
      (node (ref "U23") (pin "1") (pinfunction "VDD_1") (pintype "power_in"))
      (node (ref "U24") (pin "1") (pinfunction "VDD_1") (pintype "power_in"))
      (node (ref "U25") (pin "1") (pinfunction "VDD_1") (pintype "power_in"))
      (node (ref "U26") (pin "1") (pinfunction "VDD_1") (pintype "power_in"))
      (node (ref "U27") (pin "1") (pinfunction "VDD_1") (pintype "power_in"))
      (node (ref "U28") (pin "1") (pinfunction "VDD_1") (pintype "power_in"))
      (node (ref "U29") (pin "1") (pinfunction "VDD_1") (pintype "power_in"))
      (node (ref "U3") (pin "1") (pinfunction "VDD_1") (pintype "power_in"))
      (node (ref "U30") (pin "1") (pinfunction "VDD_1") (pintype "power_in"))
      (node (ref "U31") (pin "1") (pinfunction "VDD_1") (pintype "power_in"))
      (node (ref "U32") (pin "1") (pinfunction "VDD_1") (pintype "power_in"))
      (node (ref "U33") (pin "1") (pinfunction "VDD_1") (pintype "power_in"))
      (node (ref "U34") (pin "1") (pinfunction "VDD_1") (pintype "power_in"))
      (node (ref "U35") (pin "1") (pinfunction "VDD_1") (pintype "power_in"))
      (node (ref "U36") (pin "1") (pinfunction "VDD_1") (pintype "power_in"))
      (node (ref "U37") (pin "1") (pinfunction "VDD_1") (pintype "power_in"))
      (node (ref "U38") (pin "1") (pinfunction "VDD_1") (pintype "power_in"))
      (node (ref "U39") (pin "1") (pinfunction "VDD_1") (pintype "power_in"))
      (node (ref "U4") (pin "1") (pinfunction "VDD_1") (pintype "power_in"))
      (node (ref "U40") (pin "1") (pinfunction "VDD_1") (pintype "power_in"))
      (node (ref "U41") (pin "1") (pinfunction "VDD_1") (pintype "power_in"))
      (node (ref "U42") (pin "1") (pinfunction "VDD_1") (pintype "power_in"))
      (node (ref "U43") (pin "1") (pinfunction "VDD_1") (pintype "power_in"))
      (node (ref "U44") (pin "1") (pinfunction "VDD_1") (pintype "power_in"))
      (node (ref "U45") (pin "1") (pinfunction "VDD_1") (pintype "power_in"))
      (node (ref "U46") (pin "1") (pinfunction "VDD_1") (pintype "power_in"))
      (node (ref "U47") (pin "1") (pinfunction "VDD_1") (pintype "power_in"))
      (node (ref "U48") (pin "1") (pinfunction "VDD_1") (pintype "power_in"))
      (node (ref "U49") (pin "1") (pinfunction "VDD_1") (pintype "power_in"))
      (node (ref "U5") (pin "1") (pinfunction "VDD_1") (pintype "power_in"))
      (node (ref "U50") (pin "1") (pinfunction "VDD_1") (pintype "power_in"))
      (node (ref "U51") (pin "1") (pinfunction "VDD_1") (pintype "power_in"))
      (node (ref "U52") (pin "1") (pinfunction "VDD_1") (pintype "power_in"))
      (node (ref "U53") (pin "1") (pinfunction "VDD_1") (pintype "power_in"))
      (node (ref "U54") (pin "1") (pinfunction "VDD_1") (pintype "power_in"))
      (node (ref "U55") (pin "1") (pinfunction "VDD_1") (pintype "power_in"))
      (node (ref "U56") (pin "1") (pinfunction "VDD_1") (pintype "power_in"))
      (node (ref "U57") (pin "1") (pinfunction "VDD_1") (pintype "power_in"))
      (node (ref "U58") (pin "1") (pinfunction "VDD_1") (pintype "power_in"))
      (node (ref "U59") (pin "1") (pinfunction "VDD_1") (pintype "power_in"))
      (node (ref "U6") (pin "1") (pinfunction "VDD_1") (pintype "power_in"))
      (node (ref "U60") (pin "1") (pinfunction "VDD_1") (pintype "power_in"))
      (node (ref "U61") (pin "1") (pinfunction "VDD_1") (pintype "power_in"))
      (node (ref "U62") (pin "1") (pinfunction "VDD_1") (pintype "power_in"))
      (node (ref "U63") (pin "1") (pinfunction "VDD_1") (pintype "power_in"))
      (node (ref "U64") (pin "1") (pinfunction "VDD_1") (pintype "power_in"))
      (node (ref "U65") (pin "1") (pinfunction "VDD_1") (pintype "power_in"))
      (node (ref "U66") (pin "1") (pinfunction "VDD_1") (pintype "power_in"))
      (node (ref "U67") (pin "1") (pinfunction "VDD_1") (pintype "power_in"))
      (node (ref "U68") (pin "1") (pinfunction "VDD_1") (pintype "power_in"))
      (node (ref "U69") (pin "1") (pinfunction "VDD_1") (pintype "power_in"))
      (node (ref "U7") (pin "1") (pinfunction "VDD_1") (pintype "power_in"))
      (node (ref "U70") (pin "1") (pinfunction "VDD_1") (pintype "power_in"))
      (node (ref "U71") (pin "1") (pinfunction "VDD_1") (pintype "power_in"))
      (node (ref "U72") (pin "1") (pinfunction "VDD_1") (pintype "power_in"))
      (node (ref "U73") (pin "1") (pinfunction "VDD_1") (pintype "power_in"))
      (node (ref "U74") (pin "1") (pinfunction "VDD_1") (pintype "power_in"))
      (node (ref "U75") (pin "1") (pinfunction "VDD_1") (pintype "power_in"))
      (node (ref "U76") (pin "1") (pinfunction "VDD_1") (pintype "power_in"))
      (node (ref "U77") (pin "1") (pinfunction "VDD_1") (pintype "power_in"))
      (node (ref "U78") (pin "1") (pinfunction "VDD_1") (pintype "power_in"))
      (node (ref "U79") (pin "1") (pinfunction "VDD_1") (pintype "power_in"))
      (node (ref "U8") (pin "1") (pinfunction "VDD_1") (pintype "power_in"))
      (node (ref "U80") (pin "1") (pinfunction "VDD_1") (pintype "power_in"))
      (node (ref "U81") (pin "1") (pinfunction "VDD_1") (pintype "power_in"))
      (node (ref "U82") (pin "1") (pinfunction "VDD_1") (pintype "power_in"))
      (node (ref "U83") (pin "1") (pinfunction "VDD_1") (pintype "power_in"))
      (node (ref "U84") (pin "1") (pinfunction "VDD_1") (pintype "power_in"))
      (node (ref "U85") (pin "1") (pinfunction "VDD_1") (pintype "power_in"))
      (node (ref "U86") (pin "1") (pinfunction "VDD_1") (pintype "power_in"))
      (node (ref "U87") (pin "1") (pinfunction "VDD_1") (pintype "power_in"))
      (node (ref "U88") (pin "1") (pinfunction "VDD_1") (pintype "power_in"))
      (node (ref "U89") (pin "1") (pinfunction "VDD_1") (pintype "power_in"))
      (node (ref "U9") (pin "1") (pinfunction "VDD_1") (pintype "power_in"))
      (node (ref "U90") (pin "1") (pinfunction "VDD_1") (pintype "power_in"))
      (node (ref "U91") (pin "1") (pinfunction "VDD_1") (pintype "power_in"))
      (node (ref "U92") (pin "1") (pinfunction "VDD_1") (pintype "power_in"))
      (node (ref "U93") (pin "1") (pinfunction "VDD_1") (pintype "power_in"))
      (node (ref "U94") (pin "1") (pinfunction "VDD_1") (pintype "power_in"))
      (node (ref "U95") (pin "1") (pinfunction "VDD_1") (pintype "power_in"))
      (node (ref "U96") (pin "1") (pinfunction "VDD_1") (pintype "power_in"))
      (node (ref "U97") (pin "1") (pinfunction "VDD_1") (pintype "power_in"))
      (node (ref "U98") (pin "1") (pinfunction "VDD_1") (pintype "power_in"))
      (node (ref "U99") (pin "1") (pinfunction "VDD_1") (pintype "power_in"))
    )
    (net (code "2") (name "/LED_DRIVER") (class "Default")
      (node (ref "U0") (pin "4") (pinfunction "DIN_4") (pintype "input"))
    )
    (net (code "3") (name "GND") (class "Default")
      (node (ref "C1") (pin "2") (pinfunction "2_2") (pintype "passive"))
      (node (ref "C100") (pin "2") (pinfunction "2_2") (pintype "passive"))
      (node (ref "C101") (pin "2") (pinfunction "2_2") (pintype "passive"))
      (node (ref "C102") (pin "2") (pinfunction "2_2") (pintype "passive"))
      (node (ref "C103") (pin "2") (pinfunction "2_2") (pintype "passive"))
      (node (ref "C104") (pin "2") (pinfunction "2_2") (pintype "passive"))
      (node (ref "C105") (pin "2") (pinfunction "2_2") (pintype "passive"))
      (node (ref "C106") (pin "2") (pinfunction "2_2") (pintype "passive"))
      (node (ref "C107") (pin "2") (pinfunction "2_2") (pintype "passive"))
      (node (ref "C108") (pin "2") (pinfunction "2_2") (pintype "passive"))
      (node (ref "C109") (pin "2") (pinfunction "2_2") (pintype "passive"))
      (node (ref "C110") (pin "2") (pinfunction "2_2") (pintype "passive"))
      (node (ref "C111") (pin "2") (pinfunction "2_2") (pintype "passive"))
      (node (ref "C112") (pin "2") (pinfunction "2_2") (pintype "passive"))
      (node (ref "C113") (pin "2") (pinfunction "2_2") (pintype "passive"))
      (node (ref "C114") (pin "2") (pinfunction "2_2") (pintype "passive"))
      (node (ref "C115") (pin "2") (pinfunction "2_2") (pintype "passive"))
      (node (ref "C116") (pin "2") (pinfunction "2_2") (pintype "passive"))
      (node (ref "C117") (pin "2") (pinfunction "2_2") (pintype "passive"))
      (node (ref "C118") (pin "2") (pinfunction "2_2") (pintype "passive"))
      (node (ref "C119") (pin "2") (pinfunction "2_2") (pintype "passive"))
      (node (ref "C120") (pin "2") (pinfunction "2_2") (pintype "passive"))
      (node (ref "C121") (pin "2") (pinfunction "2_2") (pintype "passive"))
      (node (ref "C122") (pin "2") (pinfunction "2_2") (pintype "passive"))
      (node (ref "C123") (pin "2") (pinfunction "2_2") (pintype "passive"))
      (node (ref "C124") (pin "2") (pinfunction "2_2") (pintype "passive"))
      (node (ref "C125") (pin "2") (pinfunction "2_2") (pintype "passive"))
      (node (ref "C126") (pin "2") (pinfunction "2_2") (pintype "passive"))
      (node (ref "C127") (pin "2") (pinfunction "2_2") (pintype "passive"))
      (node (ref "C128") (pin "2") (pinfunction "2_2") (pintype "passive"))
      (node (ref "C129") (pin "2") (pinfunction "2_2") (pintype "passive"))
      (node (ref "C130") (pin "2") (pinfunction "2_2") (pintype "passive"))
      (node (ref "C131") (pin "2") (pinfunction "2_2") (pintype "passive"))
      (node (ref "C132") (pin "2") (pinfunction "2_2") (pintype "passive"))
      (node (ref "C133") (pin "2") (pinfunction "2_2") (pintype "passive"))
      (node (ref "C134") (pin "2") (pinfunction "2_2") (pintype "passive"))
      (node (ref "C135") (pin "2") (pinfunction "2_2") (pintype "passive"))
      (node (ref "C136") (pin "2") (pinfunction "2_2") (pintype "passive"))
      (node (ref "C137") (pin "2") (pinfunction "2_2") (pintype "passive"))
      (node (ref "C138") (pin "2") (pinfunction "2_2") (pintype "passive"))
      (node (ref "C139") (pin "2") (pinfunction "2_2") (pintype "passive"))
      (node (ref "C140") (pin "2") (pinfunction "2_2") (pintype "passive"))
      (node (ref "C141") (pin "2") (pinfunction "2_2") (pintype "passive"))
      (node (ref "C142") (pin "2") (pinfunction "2_2") (pintype "passive"))
      (node (ref "C143") (pin "2") (pinfunction "2_2") (pintype "passive"))
      (node (ref "C144") (pin "2") (pinfunction "2_2") (pintype "passive"))
      (node (ref "C145") (pin "2") (pinfunction "2_2") (pintype "passive"))
      (node (ref "C146") (pin "2") (pinfunction "2_2") (pintype "passive"))
      (node (ref "C147") (pin "2") (pinfunction "2_2") (pintype "passive"))
      (node (ref "C148") (pin "2") (pinfunction "2_2") (pintype "passive"))
      (node (ref "C149") (pin "2") (pinfunction "2_2") (pintype "passive"))
      (node (ref "C150") (pin "2") (pinfunction "2_2") (pintype "passive"))
      (node (ref "C151") (pin "2") (pinfunction "2_2") (pintype "passive"))
      (node (ref "C152") (pin "2") (pinfunction "2_2") (pintype "passive"))
      (node (ref "C153") (pin "2") (pinfunction "2_2") (pintype "passive"))
      (node (ref "C154") (pin "2") (pinfunction "2_2") (pintype "passive"))
      (node (ref "C155") (pin "2") (pinfunction "2_2") (pintype "passive"))
      (node (ref "C156") (pin "2") (pinfunction "2_2") (pintype "passive"))
      (node (ref "C157") (pin "2") (pinfunction "2_2") (pintype "passive"))
      (node (ref "C158") (pin "2") (pinfunction "2_2") (pintype "passive"))
      (node (ref "C159") (pin "2") (pinfunction "2_2") (pintype "passive"))
      (node (ref "C2") (pin "2") (pinfunction "2_2") (pintype "passive"))
      (node (ref "C20") (pin "2") (pinfunction "2_2") (pintype "passive"))
      (node (ref "C21") (pin "2") (pinfunction "2_2") (pintype "passive"))
      (node (ref "C22") (pin "2") (pinfunction "2_2") (pintype "passive"))
      (node (ref "C23") (pin "2") (pinfunction "2_2") (pintype "passive"))
      (node (ref "C24") (pin "2") (pinfunction "2_2") (pintype "passive"))
      (node (ref "C25") (pin "2") (pinfunction "2_2") (pintype "passive"))
      (node (ref "C26") (pin "2") (pinfunction "2_2") (pintype "passive"))
      (node (ref "C27") (pin "2") (pinfunction "2_2") (pintype "passive"))
      (node (ref "C28") (pin "2") (pinfunction "2_2") (pintype "passive"))
      (node (ref "C29") (pin "2") (pinfunction "2_2") (pintype "passive"))
      (node (ref "C30") (pin "2") (pinfunction "2_2") (pintype "passive"))
      (node (ref "C31") (pin "2") (pinfunction "2_2") (pintype "passive"))
      (node (ref "C32") (pin "2") (pinfunction "2_2") (pintype "passive"))
      (node (ref "C33") (pin "2") (pinfunction "2_2") (pintype "passive"))
      (node (ref "C34") (pin "2") (pinfunction "2_2") (pintype "passive"))
      (node (ref "C35") (pin "2") (pinfunction "2_2") (pintype "passive"))
      (node (ref "C36") (pin "2") (pinfunction "2_2") (pintype "passive"))
      (node (ref "C37") (pin "2") (pinfunction "2_2") (pintype "passive"))
      (node (ref "C38") (pin "2") (pinfunction "2_2") (pintype "passive"))
      (node (ref "C39") (pin "2") (pinfunction "2_2") (pintype "passive"))
      (node (ref "C40") (pin "2") (pinfunction "2_2") (pintype "passive"))
      (node (ref "C41") (pin "2") (pinfunction "2_2") (pintype "passive"))
      (node (ref "C42") (pin "2") (pinfunction "2_2") (pintype "passive"))
      (node (ref "C43") (pin "2") (pinfunction "2_2") (pintype "passive"))
      (node (ref "C44") (pin "2") (pinfunction "2_2") (pintype "passive"))
      (node (ref "C45") (pin "2") (pinfunction "2_2") (pintype "passive"))
      (node (ref "C46") (pin "2") (pinfunction "2_2") (pintype "passive"))
      (node (ref "C47") (pin "2") (pinfunction "2_2") (pintype "passive"))
      (node (ref "C48") (pin "2") (pinfunction "2_2") (pintype "passive"))
      (node (ref "C49") (pin "2") (pinfunction "2_2") (pintype "passive"))
      (node (ref "C50") (pin "2") (pinfunction "2_2") (pintype "passive"))
      (node (ref "C51") (pin "2") (pinfunction "2_2") (pintype "passive"))
      (node (ref "C52") (pin "2") (pinfunction "2_2") (pintype "passive"))
      (node (ref "C53") (pin "2") (pinfunction "2_2") (pintype "passive"))
      (node (ref "C54") (pin "2") (pinfunction "2_2") (pintype "passive"))
      (node (ref "C55") (pin "2") (pinfunction "2_2") (pintype "passive"))
      (node (ref "C56") (pin "2") (pinfunction "2_2") (pintype "passive"))
      (node (ref "C57") (pin "2") (pinfunction "2_2") (pintype "passive"))
      (node (ref "C58") (pin "2") (pinfunction "2_2") (pintype "passive"))
      (node (ref "C59") (pin "2") (pinfunction "2_2") (pintype "passive"))
      (node (ref "C60") (pin "2") (pinfunction "2_2") (pintype "passive"))
      (node (ref "C61") (pin "2") (pinfunction "2_2") (pintype "passive"))
      (node (ref "C62") (pin "2") (pinfunction "2_2") (pintype "passive"))
      (node (ref "C63") (pin "2") (pinfunction "2_2") (pintype "passive"))
      (node (ref "C64") (pin "2") (pinfunction "2_2") (pintype "passive"))
      (node (ref "C65") (pin "2") (pinfunction "2_2") (pintype "passive"))
      (node (ref "C66") (pin "2") (pinfunction "2_2") (pintype "passive"))
      (node (ref "C67") (pin "2") (pinfunction "2_2") (pintype "passive"))
      (node (ref "C68") (pin "2") (pinfunction "2_2") (pintype "passive"))
      (node (ref "C69") (pin "2") (pinfunction "2_2") (pintype "passive"))
      (node (ref "C70") (pin "2") (pinfunction "2_2") (pintype "passive"))
      (node (ref "C71") (pin "2") (pinfunction "2_2") (pintype "passive"))
      (node (ref "C72") (pin "2") (pinfunction "2_2") (pintype "passive"))
      (node (ref "C73") (pin "2") (pinfunction "2_2") (pintype "passive"))
      (node (ref "C74") (pin "2") (pinfunction "2_2") (pintype "passive"))
      (node (ref "C75") (pin "2") (pinfunction "2_2") (pintype "passive"))
      (node (ref "C76") (pin "2") (pinfunction "2_2") (pintype "passive"))
      (node (ref "C77") (pin "2") (pinfunction "2_2") (pintype "passive"))
      (node (ref "C78") (pin "2") (pinfunction "2_2") (pintype "passive"))
      (node (ref "C79") (pin "2") (pinfunction "2_2") (pintype "passive"))
      (node (ref "C80") (pin "2") (pinfunction "2_2") (pintype "passive"))
      (node (ref "C81") (pin "2") (pinfunction "2_2") (pintype "passive"))
      (node (ref "C82") (pin "2") (pinfunction "2_2") (pintype "passive"))
      (node (ref "C83") (pin "2") (pinfunction "2_2") (pintype "passive"))
      (node (ref "C84") (pin "2") (pinfunction "2_2") (pintype "passive"))
      (node (ref "C85") (pin "2") (pinfunction "2_2") (pintype "passive"))
      (node (ref "C86") (pin "2") (pinfunction "2_2") (pintype "passive"))
      (node (ref "C87") (pin "2") (pinfunction "2_2") (pintype "passive"))
      (node (ref "C88") (pin "2") (pinfunction "2_2") (pintype "passive"))
      (node (ref "C89") (pin "2") (pinfunction "2_2") (pintype "passive"))
      (node (ref "C90") (pin "2") (pinfunction "2_2") (pintype "passive"))
      (node (ref "C91") (pin "2") (pinfunction "2_2") (pintype "passive"))
      (node (ref "C92") (pin "2") (pinfunction "2_2") (pintype "passive"))
      (node (ref "C93") (pin "2") (pinfunction "2_2") (pintype "passive"))
      (node (ref "C94") (pin "2") (pinfunction "2_2") (pintype "passive"))
      (node (ref "C95") (pin "2") (pinfunction "2_2") (pintype "passive"))
      (node (ref "C96") (pin "2") (pinfunction "2_2") (pintype "passive"))
      (node (ref "C97") (pin "2") (pinfunction "2_2") (pintype "passive"))
      (node (ref "C98") (pin "2") (pinfunction "2_2") (pintype "passive"))
      (node (ref "C99") (pin "2") (pinfunction "2_2") (pintype "passive"))
      (node (ref "U0") (pin "3") (pinfunction "VSS_3") (pintype "power_in"))
      (node (ref "U1") (pin "3") (pinfunction "VSS_3") (pintype "power_in"))
      (node (ref "U10") (pin "3") (pinfunction "VSS_3") (pintype "power_in"))
      (node (ref "U100") (pin "3") (pinfunction "VSS_3") (pintype "power_in"))
      (node (ref "U101") (pin "3") (pinfunction "VSS_3") (pintype "power_in"))
      (node (ref "U102") (pin "3") (pinfunction "VSS_3") (pintype "power_in"))
      (node (ref "U103") (pin "3") (pinfunction "VSS_3") (pintype "power_in"))
      (node (ref "U104") (pin "3") (pinfunction "VSS_3") (pintype "power_in"))
      (node (ref "U105") (pin "3") (pinfunction "VSS_3") (pintype "power_in"))
      (node (ref "U106") (pin "3") (pinfunction "VSS_3") (pintype "power_in"))
      (node (ref "U107") (pin "3") (pinfunction "VSS_3") (pintype "power_in"))
      (node (ref "U108") (pin "3") (pinfunction "VSS_3") (pintype "power_in"))
      (node (ref "U109") (pin "3") (pinfunction "VSS_3") (pintype "power_in"))
      (node (ref "U11") (pin "3") (pinfunction "VSS_3") (pintype "power_in"))
      (node (ref "U110") (pin "3") (pinfunction "VSS_3") (pintype "power_in"))
      (node (ref "U111") (pin "3") (pinfunction "VSS_3") (pintype "power_in"))
      (node (ref "U112") (pin "3") (pinfunction "VSS_3") (pintype "power_in"))
      (node (ref "U113") (pin "3") (pinfunction "VSS_3") (pintype "power_in"))
      (node (ref "U114") (pin "3") (pinfunction "VSS_3") (pintype "power_in"))
      (node (ref "U115") (pin "3") (pinfunction "VSS_3") (pintype "power_in"))
      (node (ref "U116") (pin "3") (pinfunction "VSS_3") (pintype "power_in"))
      (node (ref "U117") (pin "3") (pinfunction "VSS_3") (pintype "power_in"))
      (node (ref "U118") (pin "3") (pinfunction "VSS_3") (pintype "power_in"))
      (node (ref "U119") (pin "3") (pinfunction "VSS_3") (pintype "power_in"))
      (node (ref "U12") (pin "3") (pinfunction "VSS_3") (pintype "power_in"))
      (node (ref "U120") (pin "3") (pinfunction "VSS_3") (pintype "power_in"))
      (node (ref "U121") (pin "3") (pinfunction "VSS_3") (pintype "power_in"))
      (node (ref "U122") (pin "3") (pinfunction "VSS_3") (pintype "power_in"))
      (node (ref "U123") (pin "3") (pinfunction "VSS_3") (pintype "power_in"))
      (node (ref "U124") (pin "3") (pinfunction "VSS_3") (pintype "power_in"))
      (node (ref "U125") (pin "3") (pinfunction "VSS_3") (pintype "power_in"))
      (node (ref "U126") (pin "3") (pinfunction "VSS_3") (pintype "power_in"))
      (node (ref "U127") (pin "3") (pinfunction "VSS_3") (pintype "power_in"))
      (node (ref "U128") (pin "3") (pinfunction "VSS_3") (pintype "power_in"))
      (node (ref "U129") (pin "3") (pinfunction "VSS_3") (pintype "power_in"))
      (node (ref "U13") (pin "3") (pinfunction "VSS_3") (pintype "power_in"))
      (node (ref "U130") (pin "3") (pinfunction "VSS_3") (pintype "power_in"))
      (node (ref "U131") (pin "3") (pinfunction "VSS_3") (pintype "power_in"))
      (node (ref "U132") (pin "3") (pinfunction "VSS_3") (pintype "power_in"))
      (node (ref "U133") (pin "3") (pinfunction "VSS_3") (pintype "power_in"))
      (node (ref "U134") (pin "3") (pinfunction "VSS_3") (pintype "power_in"))
      (node (ref "U135") (pin "3") (pinfunction "VSS_3") (pintype "power_in"))
      (node (ref "U136") (pin "3") (pinfunction "VSS_3") (pintype "power_in"))
      (node (ref "U137") (pin "3") (pinfunction "VSS_3") (pintype "power_in"))
      (node (ref "U138") (pin "3") (pinfunction "VSS_3") (pintype "power_in"))
      (node (ref "U139") (pin "3") (pinfunction "VSS_3") (pintype "power_in"))
      (node (ref "U14") (pin "3") (pinfunction "VSS_3") (pintype "power_in"))
      (node (ref "U140") (pin "3") (pinfunction "VSS_3") (pintype "power_in"))
      (node (ref "U141") (pin "3") (pinfunction "VSS_3") (pintype "power_in"))
      (node (ref "U15") (pin "3") (pinfunction "VSS_3") (pintype "power_in"))
      (node (ref "U16") (pin "3") (pinfunction "VSS_3") (pintype "power_in"))
      (node (ref "U17") (pin "3") (pinfunction "VSS_3") (pintype "power_in"))
      (node (ref "U18") (pin "3") (pinfunction "VSS_3") (pintype "power_in"))
      (node (ref "U19") (pin "3") (pinfunction "VSS_3") (pintype "power_in"))
      (node (ref "U2") (pin "3") (pinfunction "VSS_3") (pintype "power_in"))
      (node (ref "U20") (pin "3") (pinfunction "VSS_3") (pintype "power_in"))
      (node (ref "U21") (pin "3") (pinfunction "VSS_3") (pintype "power_in"))
      (node (ref "U22") (pin "3") (pinfunction "VSS_3") (pintype "power_in"))
      (node (ref "U23") (pin "3") (pinfunction "VSS_3") (pintype "power_in"))
      (node (ref "U24") (pin "3") (pinfunction "VSS_3") (pintype "power_in"))
      (node (ref "U25") (pin "3") (pinfunction "VSS_3") (pintype "power_in"))
      (node (ref "U26") (pin "3") (pinfunction "VSS_3") (pintype "power_in"))
      (node (ref "U27") (pin "3") (pinfunction "VSS_3") (pintype "power_in"))
      (node (ref "U28") (pin "3") (pinfunction "VSS_3") (pintype "power_in"))
      (node (ref "U29") (pin "3") (pinfunction "VSS_3") (pintype "power_in"))
      (node (ref "U3") (pin "3") (pinfunction "VSS_3") (pintype "power_in"))
      (node (ref "U30") (pin "3") (pinfunction "VSS_3") (pintype "power_in"))
      (node (ref "U31") (pin "3") (pinfunction "VSS_3") (pintype "power_in"))
      (node (ref "U32") (pin "3") (pinfunction "VSS_3") (pintype "power_in"))
      (node (ref "U33") (pin "3") (pinfunction "VSS_3") (pintype "power_in"))
      (node (ref "U34") (pin "3") (pinfunction "VSS_3") (pintype "power_in"))
      (node (ref "U35") (pin "3") (pinfunction "VSS_3") (pintype "power_in"))
      (node (ref "U36") (pin "3") (pinfunction "VSS_3") (pintype "power_in"))
      (node (ref "U37") (pin "3") (pinfunction "VSS_3") (pintype "power_in"))
      (node (ref "U38") (pin "3") (pinfunction "VSS_3") (pintype "power_in"))
      (node (ref "U39") (pin "3") (pinfunction "VSS_3") (pintype "power_in"))
      (node (ref "U4") (pin "3") (pinfunction "VSS_3") (pintype "power_in"))
      (node (ref "U40") (pin "3") (pinfunction "VSS_3") (pintype "power_in"))
      (node (ref "U41") (pin "3") (pinfunction "VSS_3") (pintype "power_in"))
      (node (ref "U42") (pin "3") (pinfunction "VSS_3") (pintype "power_in"))
      (node (ref "U43") (pin "3") (pinfunction "VSS_3") (pintype "power_in"))
      (node (ref "U44") (pin "3") (pinfunction "VSS_3") (pintype "power_in"))
      (node (ref "U45") (pin "3") (pinfunction "VSS_3") (pintype "power_in"))
      (node (ref "U46") (pin "3") (pinfunction "VSS_3") (pintype "power_in"))
      (node (ref "U47") (pin "3") (pinfunction "VSS_3") (pintype "power_in"))
      (node (ref "U48") (pin "3") (pinfunction "VSS_3") (pintype "power_in"))
      (node (ref "U49") (pin "3") (pinfunction "VSS_3") (pintype "power_in"))
      (node (ref "U5") (pin "3") (pinfunction "VSS_3") (pintype "power_in"))
      (node (ref "U50") (pin "3") (pinfunction "VSS_3") (pintype "power_in"))
      (node (ref "U51") (pin "3") (pinfunction "VSS_3") (pintype "power_in"))
      (node (ref "U52") (pin "3") (pinfunction "VSS_3") (pintype "power_in"))
      (node (ref "U53") (pin "3") (pinfunction "VSS_3") (pintype "power_in"))
      (node (ref "U54") (pin "3") (pinfunction "VSS_3") (pintype "power_in"))
      (node (ref "U55") (pin "3") (pinfunction "VSS_3") (pintype "power_in"))
      (node (ref "U56") (pin "3") (pinfunction "VSS_3") (pintype "power_in"))
      (node (ref "U57") (pin "3") (pinfunction "VSS_3") (pintype "power_in"))
      (node (ref "U58") (pin "3") (pinfunction "VSS_3") (pintype "power_in"))
      (node (ref "U59") (pin "3") (pinfunction "VSS_3") (pintype "power_in"))
      (node (ref "U6") (pin "3") (pinfunction "VSS_3") (pintype "power_in"))
      (node (ref "U60") (pin "3") (pinfunction "VSS_3") (pintype "power_in"))
      (node (ref "U61") (pin "3") (pinfunction "VSS_3") (pintype "power_in"))
      (node (ref "U62") (pin "3") (pinfunction "VSS_3") (pintype "power_in"))
      (node (ref "U63") (pin "3") (pinfunction "VSS_3") (pintype "power_in"))
      (node (ref "U64") (pin "3") (pinfunction "VSS_3") (pintype "power_in"))
      (node (ref "U65") (pin "3") (pinfunction "VSS_3") (pintype "power_in"))
      (node (ref "U66") (pin "3") (pinfunction "VSS_3") (pintype "power_in"))
      (node (ref "U67") (pin "3") (pinfunction "VSS_3") (pintype "power_in"))
      (node (ref "U68") (pin "3") (pinfunction "VSS_3") (pintype "power_in"))
      (node (ref "U69") (pin "3") (pinfunction "VSS_3") (pintype "power_in"))
      (node (ref "U7") (pin "3") (pinfunction "VSS_3") (pintype "power_in"))
      (node (ref "U70") (pin "3") (pinfunction "VSS_3") (pintype "power_in"))
      (node (ref "U71") (pin "3") (pinfunction "VSS_3") (pintype "power_in"))
      (node (ref "U72") (pin "3") (pinfunction "VSS_3") (pintype "power_in"))
      (node (ref "U73") (pin "3") (pinfunction "VSS_3") (pintype "power_in"))
      (node (ref "U74") (pin "3") (pinfunction "VSS_3") (pintype "power_in"))
      (node (ref "U75") (pin "3") (pinfunction "VSS_3") (pintype "power_in"))
      (node (ref "U76") (pin "3") (pinfunction "VSS_3") (pintype "power_in"))
      (node (ref "U77") (pin "3") (pinfunction "VSS_3") (pintype "power_in"))
      (node (ref "U78") (pin "3") (pinfunction "VSS_3") (pintype "power_in"))
      (node (ref "U79") (pin "3") (pinfunction "VSS_3") (pintype "power_in"))
      (node (ref "U8") (pin "3") (pinfunction "VSS_3") (pintype "power_in"))
      (node (ref "U80") (pin "3") (pinfunction "VSS_3") (pintype "power_in"))
      (node (ref "U81") (pin "3") (pinfunction "VSS_3") (pintype "power_in"))
      (node (ref "U82") (pin "3") (pinfunction "VSS_3") (pintype "power_in"))
      (node (ref "U83") (pin "3") (pinfunction "VSS_3") (pintype "power_in"))
      (node (ref "U84") (pin "3") (pinfunction "VSS_3") (pintype "power_in"))
      (node (ref "U85") (pin "3") (pinfunction "VSS_3") (pintype "power_in"))
      (node (ref "U86") (pin "3") (pinfunction "VSS_3") (pintype "power_in"))
      (node (ref "U87") (pin "3") (pinfunction "VSS_3") (pintype "power_in"))
      (node (ref "U88") (pin "3") (pinfunction "VSS_3") (pintype "power_in"))
      (node (ref "U89") (pin "3") (pinfunction "VSS_3") (pintype "power_in"))
      (node (ref "U9") (pin "3") (pinfunction "VSS_3") (pintype "power_in"))
      (node (ref "U90") (pin "3") (pinfunction "VSS_3") (pintype "power_in"))
      (node (ref "U91") (pin "3") (pinfunction "VSS_3") (pintype "power_in"))
      (node (ref "U92") (pin "3") (pinfunction "VSS_3") (pintype "power_in"))
      (node (ref "U93") (pin "3") (pinfunction "VSS_3") (pintype "power_in"))
      (node (ref "U94") (pin "3") (pinfunction "VSS_3") (pintype "power_in"))
      (node (ref "U95") (pin "3") (pinfunction "VSS_3") (pintype "power_in"))
      (node (ref "U96") (pin "3") (pinfunction "VSS_3") (pintype "power_in"))
      (node (ref "U97") (pin "3") (pinfunction "VSS_3") (pintype "power_in"))
      (node (ref "U98") (pin "3") (pinfunction "VSS_3") (pintype "power_in"))
      (node (ref "U99") (pin "3") (pinfunction "VSS_3") (pintype "power_in"))
    )
    (net (code "4") (name "Net-(U0-DOUT)") (class "Default")
      (node (ref "U0") (pin "2") (pinfunction "DOUT_2") (pintype "output"))
      (node (ref "U1") (pin "4") (pinfunction "DIN_4") (pintype "input"))
    )
    (net (code "5") (name "Net-(U1-DOUT)") (class "Default")
      (node (ref "U1") (pin "2") (pinfunction "DOUT_2") (pintype "output"))
      (node (ref "U2") (pin "4") (pinfunction "DIN_4") (pintype "input"))
    )
    (net (code "6") (name "Net-(U2-DOUT)") (class "Default")
      (node (ref "U2") (pin "2") (pinfunction "DOUT_2") (pintype "output"))
      (node (ref "U3") (pin "4") (pinfunction "DIN_4") (pintype "input"))
    )
    (net (code "7") (name "Net-(U3-DOUT)") (class "Default")
      (node (ref "U3") (pin "2") (pinfunction "DOUT_2") (pintype "output"))
      (node (ref "U4") (pin "4") (pinfunction "DIN_4") (pintype "input"))
    )
    (net (code "8") (name "Net-(U4-DOUT)") (class "Default")
      (node (ref "U4") (pin "2") (pinfunction "DOUT_2") (pintype "output"))
      (node (ref "U5") (pin "4") (pinfunction "DIN_4") (pintype "input"))
    )
    (net (code "9") (name "Net-(U5-DOUT)") (class "Default")
      (node (ref "U5") (pin "2") (pinfunction "DOUT_2") (pintype "output"))
      (node (ref "U6") (pin "4") (pinfunction "DIN_4") (pintype "input"))
    )
    (net (code "10") (name "Net-(U6-DOUT)") (class "Default")
      (node (ref "U6") (pin "2") (pinfunction "DOUT_2") (pintype "output"))
      (node (ref "U7") (pin "4") (pinfunction "DIN_4") (pintype "input"))
    )
    (net (code "11") (name "Net-(U7-DOUT)") (class "Default")
      (node (ref "U7") (pin "2") (pinfunction "DOUT_2") (pintype "output"))
      (node (ref "U8") (pin "4") (pinfunction "DIN_4") (pintype "input"))
    )
    (net (code "12") (name "Net-(U8-DOUT)") (class "Default")
      (node (ref "U8") (pin "2") (pinfunction "DOUT_2") (pintype "output"))
      (node (ref "U9") (pin "4") (pinfunction "DIN_4") (pintype "input"))
    )
    (net (code "13") (name "Net-(U10-DIN)") (class "Default")
      (node (ref "U10") (pin "4") (pinfunction "DIN_4") (pintype "input"))
      (node (ref "U9") (pin "2") (pinfunction "DOUT_2") (pintype "output"))
    )
    (net (code "14") (name "Net-(U10-DOUT)") (class "Default")
      (node (ref "U10") (pin "2") (pinfunction "DOUT_2") (pintype "output"))
      (node (ref "U11") (pin "4") (pinfunction "DIN_4") (pintype "input"))
    )
    (net (code "15") (name "Net-(U11-DOUT)") (class "Default")
      (node (ref "U11") (pin "2") (pinfunction "DOUT_2") (pintype "output"))
      (node (ref "U12") (pin "4") (pinfunction "DIN_4") (pintype "input"))
    )
    (net (code "16") (name "Net-(U12-DOUT)") (class "Default")
      (node (ref "U12") (pin "2") (pinfunction "DOUT_2") (pintype "output"))
      (node (ref "U13") (pin "4") (pinfunction "DIN_4") (pintype "input"))
    )
    (net (code "17") (name "Net-(U13-DOUT)") (class "Default")
      (node (ref "U13") (pin "2") (pinfunction "DOUT_2") (pintype "output"))
      (node (ref "U14") (pin "4") (pinfunction "DIN_4") (pintype "input"))
    )
    (net (code "18") (name "Net-(U14-DOUT)") (class "Default")
      (node (ref "U14") (pin "2") (pinfunction "DOUT_2") (pintype "output"))
      (node (ref "U15") (pin "4") (pinfunction "DIN_4") (pintype "input"))
    )
    (net (code "19") (name "Net-(U15-DOUT)") (class "Default")
      (node (ref "U15") (pin "2") (pinfunction "DOUT_2") (pintype "output"))
      (node (ref "U16") (pin "4") (pinfunction "DIN_4") (pintype "input"))
    )
    (net (code "20") (name "Net-(U16-DOUT)") (class "Default")
      (node (ref "U16") (pin "2") (pinfunction "DOUT_2") (pintype "output"))
      (node (ref "U17") (pin "4") (pinfunction "DIN_4") (pintype "input"))
    )
    (net (code "21") (name "Net-(U17-DOUT)") (class "Default")
      (node (ref "U17") (pin "2") (pinfunction "DOUT_2") (pintype "output"))
      (node (ref "U18") (pin "4") (pinfunction "DIN_4") (pintype "input"))
    )
    (net (code "22") (name "Net-(U18-DOUT)") (class "Default")
      (node (ref "U18") (pin "2") (pinfunction "DOUT_2") (pintype "output"))
      (node (ref "U19") (pin "4") (pinfunction "DIN_4") (pintype "input"))
    )
    (net (code "23") (name "Net-(U19-DOUT)") (class "Default")
      (node (ref "U19") (pin "2") (pinfunction "DOUT_2") (pintype "output"))
      (node (ref "U20") (pin "4") (pinfunction "DIN_4") (pintype "input"))
    )
    (net (code "24") (name "Net-(U20-DOUT)") (class "Default")
      (node (ref "U20") (pin "2") (pinfunction "DOUT_2") (pintype "output"))
      (node (ref "U21") (pin "4") (pinfunction "DIN_4") (pintype "input"))
    )
    (net (code "25") (name "Net-(U21-DOUT)") (class "Default")
      (node (ref "U21") (pin "2") (pinfunction "DOUT_2") (pintype "output"))
      (node (ref "U22") (pin "4") (pinfunction "DIN_4") (pintype "input"))
    )
    (net (code "26") (name "Net-(U22-DOUT)") (class "Default")
      (node (ref "U22") (pin "2") (pinfunction "DOUT_2") (pintype "output"))
      (node (ref "U23") (pin "4") (pinfunction "DIN_4") (pintype "input"))
    )
    (net (code "27") (name "Net-(U23-DOUT)") (class "Default")
      (node (ref "U23") (pin "2") (pinfunction "DOUT_2") (pintype "output"))
      (node (ref "U24") (pin "4") (pinfunction "DIN_4") (pintype "input"))
    )
    (net (code "28") (name "Net-(U24-DOUT)") (class "Default")
      (node (ref "U24") (pin "2") (pinfunction "DOUT_2") (pintype "output"))
      (node (ref "U25") (pin "4") (pinfunction "DIN_4") (pintype "input"))
    )
    (net (code "29") (name "Net-(U25-DOUT)") (class "Default")
      (node (ref "U25") (pin "2") (pinfunction "DOUT_2") (pintype "output"))
      (node (ref "U26") (pin "4") (pinfunction "DIN_4") (pintype "input"))
    )
    (net (code "30") (name "Net-(U26-DOUT)") (class "Default")
      (node (ref "U26") (pin "2") (pinfunction "DOUT_2") (pintype "output"))
      (node (ref "U27") (pin "4") (pinfunction "DIN_4") (pintype "input"))
    )
    (net (code "31") (name "Net-(U27-DOUT)") (class "Default")
      (node (ref "U27") (pin "2") (pinfunction "DOUT_2") (pintype "output"))
      (node (ref "U28") (pin "4") (pinfunction "DIN_4") (pintype "input"))
    )
    (net (code "32") (name "Net-(U28-DOUT)") (class "Default")
      (node (ref "U28") (pin "2") (pinfunction "DOUT_2") (pintype "output"))
      (node (ref "U29") (pin "4") (pinfunction "DIN_4") (pintype "input"))
    )
    (net (code "33") (name "Net-(U29-DOUT)") (class "Default")
      (node (ref "U29") (pin "2") (pinfunction "DOUT_2") (pintype "output"))
      (node (ref "U30") (pin "4") (pinfunction "DIN_4") (pintype "input"))
    )
    (net (code "34") (name "Net-(U30-DOUT)") (class "Default")
      (node (ref "U30") (pin "2") (pinfunction "DOUT_2") (pintype "output"))
      (node (ref "U31") (pin "4") (pinfunction "DIN_4") (pintype "input"))
    )
    (net (code "35") (name "Net-(U31-DOUT)") (class "Default")
      (node (ref "U31") (pin "2") (pinfunction "DOUT_2") (pintype "output"))
      (node (ref "U32") (pin "4") (pinfunction "DIN_4") (pintype "input"))
    )
    (net (code "36") (name "Net-(U32-DOUT)") (class "Default")
      (node (ref "U32") (pin "2") (pinfunction "DOUT_2") (pintype "output"))
      (node (ref "U33") (pin "4") (pinfunction "DIN_4") (pintype "input"))
    )
    (net (code "37") (name "Net-(U33-DOUT)") (class "Default")
      (node (ref "U33") (pin "2") (pinfunction "DOUT_2") (pintype "output"))
      (node (ref "U34") (pin "4") (pinfunction "DIN_4") (pintype "input"))
    )
    (net (code "38") (name "Net-(U34-DOUT)") (class "Default")
      (node (ref "U34") (pin "2") (pinfunction "DOUT_2") (pintype "output"))
      (node (ref "U35") (pin "4") (pinfunction "DIN_4") (pintype "input"))
    )
    (net (code "39") (name "Net-(U35-DOUT)") (class "Default")
      (node (ref "U35") (pin "2") (pinfunction "DOUT_2") (pintype "output"))
      (node (ref "U36") (pin "4") (pinfunction "DIN_4") (pintype "input"))
    )
    (net (code "40") (name "Net-(U36-DOUT)") (class "Default")
      (node (ref "U36") (pin "2") (pinfunction "DOUT_2") (pintype "output"))
      (node (ref "U37") (pin "4") (pinfunction "DIN_4") (pintype "input"))
    )
    (net (code "41") (name "Net-(U37-DOUT)") (class "Default")
      (node (ref "U37") (pin "2") (pinfunction "DOUT_2") (pintype "output"))
      (node (ref "U38") (pin "4") (pinfunction "DIN_4") (pintype "input"))
    )
    (net (code "42") (name "Net-(U38-DOUT)") (class "Default")
      (node (ref "U38") (pin "2") (pinfunction "DOUT_2") (pintype "output"))
      (node (ref "U39") (pin "4") (pinfunction "DIN_4") (pintype "input"))
    )
    (net (code "43") (name "Net-(U39-DOUT)") (class "Default")
      (node (ref "U39") (pin "2") (pinfunction "DOUT_2") (pintype "output"))
      (node (ref "U40") (pin "4") (pinfunction "DIN_4") (pintype "input"))
    )
    (net (code "44") (name "Net-(U40-DOUT)") (class "Default")
      (node (ref "U40") (pin "2") (pinfunction "DOUT_2") (pintype "output"))
      (node (ref "U41") (pin "4") (pinfunction "DIN_4") (pintype "input"))
    )
    (net (code "45") (name "Net-(U41-DOUT)") (class "Default")
      (node (ref "U41") (pin "2") (pinfunction "DOUT_2") (pintype "output"))
      (node (ref "U42") (pin "4") (pinfunction "DIN_4") (pintype "input"))
    )
    (net (code "46") (name "Net-(U42-DOUT)") (class "Default")
      (node (ref "U42") (pin "2") (pinfunction "DOUT_2") (pintype "output"))
      (node (ref "U43") (pin "4") (pinfunction "DIN_4") (pintype "input"))
    )
    (net (code "47") (name "Net-(U43-DOUT)") (class "Default")
      (node (ref "U43") (pin "2") (pinfunction "DOUT_2") (pintype "output"))
      (node (ref "U44") (pin "4") (pinfunction "DIN_4") (pintype "input"))
    )
    (net (code "48") (name "Net-(U44-DOUT)") (class "Default")
      (node (ref "U44") (pin "2") (pinfunction "DOUT_2") (pintype "output"))
      (node (ref "U45") (pin "4") (pinfunction "DIN_4") (pintype "input"))
    )
    (net (code "49") (name "Net-(U45-DOUT)") (class "Default")
      (node (ref "U45") (pin "2") (pinfunction "DOUT_2") (pintype "output"))
      (node (ref "U46") (pin "4") (pinfunction "DIN_4") (pintype "input"))
    )
    (net (code "50") (name "Net-(U46-DOUT)") (class "Default")
      (node (ref "U46") (pin "2") (pinfunction "DOUT_2") (pintype "output"))
      (node (ref "U47") (pin "4") (pinfunction "DIN_4") (pintype "input"))
    )
    (net (code "51") (name "Net-(U47-DOUT)") (class "Default")
      (node (ref "U47") (pin "2") (pinfunction "DOUT_2") (pintype "output"))
      (node (ref "U48") (pin "4") (pinfunction "DIN_4") (pintype "input"))
    )
    (net (code "52") (name "Net-(U48-DOUT)") (class "Default")
      (node (ref "U48") (pin "2") (pinfunction "DOUT_2") (pintype "output"))
      (node (ref "U49") (pin "4") (pinfunction "DIN_4") (pintype "input"))
    )
    (net (code "53") (name "Net-(U49-DOUT)") (class "Default")
      (node (ref "U49") (pin "2") (pinfunction "DOUT_2") (pintype "output"))
      (node (ref "U50") (pin "4") (pinfunction "DIN_4") (pintype "input"))
    )
    (net (code "54") (name "Net-(U50-DOUT)") (class "Default")
      (node (ref "U50") (pin "2") (pinfunction "DOUT_2") (pintype "output"))
      (node (ref "U51") (pin "4") (pinfunction "DIN_4") (pintype "input"))
    )
    (net (code "55") (name "Net-(U51-DOUT)") (class "Default")
      (node (ref "U51") (pin "2") (pinfunction "DOUT_2") (pintype "output"))
      (node (ref "U52") (pin "4") (pinfunction "DIN_4") (pintype "input"))
    )
    (net (code "56") (name "Net-(U52-DOUT)") (class "Default")
      (node (ref "U52") (pin "2") (pinfunction "DOUT_2") (pintype "output"))
      (node (ref "U53") (pin "4") (pinfunction "DIN_4") (pintype "input"))
    )
    (net (code "57") (name "Net-(U53-DOUT)") (class "Default")
      (node (ref "U53") (pin "2") (pinfunction "DOUT_2") (pintype "output"))
      (node (ref "U54") (pin "4") (pinfunction "DIN_4") (pintype "input"))
    )
    (net (code "58") (name "Net-(U54-DOUT)") (class "Default")
      (node (ref "U54") (pin "2") (pinfunction "DOUT_2") (pintype "output"))
      (node (ref "U55") (pin "4") (pinfunction "DIN_4") (pintype "input"))
    )
    (net (code "59") (name "Net-(U55-DOUT)") (class "Default")
      (node (ref "U55") (pin "2") (pinfunction "DOUT_2") (pintype "output"))
      (node (ref "U56") (pin "4") (pinfunction "DIN_4") (pintype "input"))
    )
    (net (code "60") (name "Net-(U56-DOUT)") (class "Default")
      (node (ref "U56") (pin "2") (pinfunction "DOUT_2") (pintype "output"))
      (node (ref "U57") (pin "4") (pinfunction "DIN_4") (pintype "input"))
    )
    (net (code "61") (name "Net-(U57-DOUT)") (class "Default")
      (node (ref "U57") (pin "2") (pinfunction "DOUT_2") (pintype "output"))
      (node (ref "U58") (pin "4") (pinfunction "DIN_4") (pintype "input"))
    )
    (net (code "62") (name "Net-(U58-DOUT)") (class "Default")
      (node (ref "U58") (pin "2") (pinfunction "DOUT_2") (pintype "output"))
      (node (ref "U59") (pin "4") (pinfunction "DIN_4") (pintype "input"))
    )
    (net (code "63") (name "Net-(U59-DOUT)") (class "Default")
      (node (ref "U59") (pin "2") (pinfunction "DOUT_2") (pintype "output"))
      (node (ref "U60") (pin "4") (pinfunction "DIN_4") (pintype "input"))
    )
    (net (code "64") (name "Net-(U60-DOUT)") (class "Default")
      (node (ref "U60") (pin "2") (pinfunction "DOUT_2") (pintype "output"))
      (node (ref "U61") (pin "4") (pinfunction "DIN_4") (pintype "input"))
    )
    (net (code "65") (name "Net-(U61-DOUT)") (class "Default")
      (node (ref "U61") (pin "2") (pinfunction "DOUT_2") (pintype "output"))
      (node (ref "U62") (pin "4") (pinfunction "DIN_4") (pintype "input"))
    )
    (net (code "66") (name "Net-(U62-DOUT)") (class "Default")
      (node (ref "U62") (pin "2") (pinfunction "DOUT_2") (pintype "output"))
      (node (ref "U63") (pin "4") (pinfunction "DIN_4") (pintype "input"))
    )
    (net (code "67") (name "Net-(U63-DOUT)") (class "Default")
      (node (ref "U63") (pin "2") (pinfunction "DOUT_2") (pintype "output"))
      (node (ref "U64") (pin "4") (pinfunction "DIN_4") (pintype "input"))
    )
    (net (code "68") (name "Net-(U64-DOUT)") (class "Default")
      (node (ref "U64") (pin "2") (pinfunction "DOUT_2") (pintype "output"))
      (node (ref "U65") (pin "4") (pinfunction "DIN_4") (pintype "input"))
    )
    (net (code "69") (name "Net-(U65-DOUT)") (class "Default")
      (node (ref "U65") (pin "2") (pinfunction "DOUT_2") (pintype "output"))
      (node (ref "U66") (pin "4") (pinfunction "DIN_4") (pintype "input"))
    )
    (net (code "70") (name "Net-(U66-DOUT)") (class "Default")
      (node (ref "U66") (pin "2") (pinfunction "DOUT_2") (pintype "output"))
      (node (ref "U67") (pin "4") (pinfunction "DIN_4") (pintype "input"))
    )
    (net (code "71") (name "Net-(U67-DOUT)") (class "Default")
      (node (ref "U67") (pin "2") (pinfunction "DOUT_2") (pintype "output"))
      (node (ref "U68") (pin "4") (pinfunction "DIN_4") (pintype "input"))
    )
    (net (code "72") (name "Net-(U68-DOUT)") (class "Default")
      (node (ref "U68") (pin "2") (pinfunction "DOUT_2") (pintype "output"))
      (node (ref "U69") (pin "4") (pinfunction "DIN_4") (pintype "input"))
    )
    (net (code "73") (name "Net-(U69-DOUT)") (class "Default")
      (node (ref "U69") (pin "2") (pinfunction "DOUT_2") (pintype "output"))
      (node (ref "U70") (pin "4") (pinfunction "DIN_4") (pintype "input"))
    )
    (net (code "74") (name "Net-(U70-DOUT)") (class "Default")
      (node (ref "U70") (pin "2") (pinfunction "DOUT_2") (pintype "output"))
      (node (ref "U71") (pin "4") (pinfunction "DIN_4") (pintype "input"))
    )
    (net (code "75") (name "Net-(U71-DOUT)") (class "Default")
      (node (ref "U71") (pin "2") (pinfunction "DOUT_2") (pintype "output"))
      (node (ref "U72") (pin "4") (pinfunction "DIN_4") (pintype "input"))
    )
    (net (code "76") (name "Net-(U72-DOUT)") (class "Default")
      (node (ref "U72") (pin "2") (pinfunction "DOUT_2") (pintype "output"))
      (node (ref "U73") (pin "4") (pinfunction "DIN_4") (pintype "input"))
    )
    (net (code "77") (name "Net-(U73-DOUT)") (class "Default")
      (node (ref "U73") (pin "2") (pinfunction "DOUT_2") (pintype "output"))
      (node (ref "U74") (pin "4") (pinfunction "DIN_4") (pintype "input"))
    )
    (net (code "78") (name "Net-(U74-DOUT)") (class "Default")
      (node (ref "U74") (pin "2") (pinfunction "DOUT_2") (pintype "output"))
      (node (ref "U75") (pin "4") (pinfunction "DIN_4") (pintype "input"))
    )
    (net (code "79") (name "Net-(U75-DOUT)") (class "Default")
      (node (ref "U75") (pin "2") (pinfunction "DOUT_2") (pintype "output"))
      (node (ref "U76") (pin "4") (pinfunction "DIN_4") (pintype "input"))
    )
    (net (code "80") (name "Net-(U76-DOUT)") (class "Default")
      (node (ref "U76") (pin "2") (pinfunction "DOUT_2") (pintype "output"))
      (node (ref "U77") (pin "4") (pinfunction "DIN_4") (pintype "input"))
    )
    (net (code "81") (name "Net-(U77-DOUT)") (class "Default")
      (node (ref "U77") (pin "2") (pinfunction "DOUT_2") (pintype "output"))
      (node (ref "U78") (pin "4") (pinfunction "DIN_4") (pintype "input"))
    )
    (net (code "82") (name "Net-(U78-DOUT)") (class "Default")
      (node (ref "U78") (pin "2") (pinfunction "DOUT_2") (pintype "output"))
      (node (ref "U79") (pin "4") (pinfunction "DIN_4") (pintype "input"))
    )
    (net (code "83") (name "Net-(U79-DOUT)") (class "Default")
      (node (ref "U79") (pin "2") (pinfunction "DOUT_2") (pintype "output"))
      (node (ref "U80") (pin "4") (pinfunction "DIN_4") (pintype "input"))
    )
    (net (code "84") (name "Net-(U80-DOUT)") (class "Default")
      (node (ref "U80") (pin "2") (pinfunction "DOUT_2") (pintype "output"))
      (node (ref "U81") (pin "4") (pinfunction "DIN_4") (pintype "input"))
    )
    (net (code "85") (name "Net-(U81-DOUT)") (class "Default")
      (node (ref "U81") (pin "2") (pinfunction "DOUT_2") (pintype "output"))
      (node (ref "U82") (pin "4") (pinfunction "DIN_4") (pintype "input"))
    )
    (net (code "86") (name "Net-(U82-DOUT)") (class "Default")
      (node (ref "U82") (pin "2") (pinfunction "DOUT_2") (pintype "output"))
      (node (ref "U83") (pin "4") (pinfunction "DIN_4") (pintype "input"))
    )
    (net (code "87") (name "Net-(U83-DOUT)") (class "Default")
      (node (ref "U83") (pin "2") (pinfunction "DOUT_2") (pintype "output"))
      (node (ref "U84") (pin "4") (pinfunction "DIN_4") (pintype "input"))
    )
    (net (code "88") (name "Net-(U84-DOUT)") (class "Default")
      (node (ref "U84") (pin "2") (pinfunction "DOUT_2") (pintype "output"))
      (node (ref "U85") (pin "4") (pinfunction "DIN_4") (pintype "input"))
    )
    (net (code "89") (name "Net-(U85-DOUT)") (class "Default")
      (node (ref "U85") (pin "2") (pinfunction "DOUT_2") (pintype "output"))
      (node (ref "U86") (pin "4") (pinfunction "DIN_4") (pintype "input"))
    )
    (net (code "90") (name "Net-(U86-DOUT)") (class "Default")
      (node (ref "U86") (pin "2") (pinfunction "DOUT_2") (pintype "output"))
      (node (ref "U87") (pin "4") (pinfunction "DIN_4") (pintype "input"))
    )
    (net (code "91") (name "Net-(U87-DOUT)") (class "Default")
      (node (ref "U87") (pin "2") (pinfunction "DOUT_2") (pintype "output"))
      (node (ref "U88") (pin "4") (pinfunction "DIN_4") (pintype "input"))
    )
    (net (code "92") (name "Net-(U88-DOUT)") (class "Default")
      (node (ref "U88") (pin "2") (pinfunction "DOUT_2") (pintype "output"))
      (node (ref "U89") (pin "4") (pinfunction "DIN_4") (pintype "input"))
    )
    (net (code "93") (name "Net-(U89-DOUT)") (class "Default")
      (node (ref "U89") (pin "2") (pinfunction "DOUT_2") (pintype "output"))
      (node (ref "U90") (pin "4") (pinfunction "DIN_4") (pintype "input"))
    )
    (net (code "94") (name "Net-(U90-DOUT)") (class "Default")
      (node (ref "U90") (pin "2") (pinfunction "DOUT_2") (pintype "output"))
      (node (ref "U91") (pin "4") (pinfunction "DIN_4") (pintype "input"))
    )
    (net (code "95") (name "Net-(U91-DOUT)") (class "Default")
      (node (ref "U91") (pin "2") (pinfunction "DOUT_2") (pintype "output"))
      (node (ref "U92") (pin "4") (pinfunction "DIN_4") (pintype "input"))
    )
    (net (code "96") (name "Net-(U92-DOUT)") (class "Default")
      (node (ref "U92") (pin "2") (pinfunction "DOUT_2") (pintype "output"))
      (node (ref "U93") (pin "4") (pinfunction "DIN_4") (pintype "input"))
    )
    (net (code "97") (name "Net-(U93-DOUT)") (class "Default")
      (node (ref "U93") (pin "2") (pinfunction "DOUT_2") (pintype "output"))
      (node (ref "U94") (pin "4") (pinfunction "DIN_4") (pintype "input"))
    )
    (net (code "98") (name "Net-(U94-DOUT)") (class "Default")
      (node (ref "U94") (pin "2") (pinfunction "DOUT_2") (pintype "output"))
      (node (ref "U95") (pin "4") (pinfunction "DIN_4") (pintype "input"))
    )
    (net (code "99") (name "Net-(U95-DOUT)") (class "Default")
      (node (ref "U95") (pin "2") (pinfunction "DOUT_2") (pintype "output"))
      (node (ref "U96") (pin "4") (pinfunction "DIN_4") (pintype "input"))
    )
    (net (code "100") (name "Net-(U96-DOUT)") (class "Default")
      (node (ref "U96") (pin "2") (pinfunction "DOUT_2") (pintype "output"))
      (node (ref "U97") (pin "4") (pinfunction "DIN_4") (pintype "input"))
    )
    (net (code "101") (name "Net-(U97-DOUT)") (class "Default")
      (node (ref "U97") (pin "2") (pinfunction "DOUT_2") (pintype "output"))
      (node (ref "U98") (pin "4") (pinfunction "DIN_4") (pintype "input"))
    )
    (net (code "102") (name "Net-(U98-DOUT)") (class "Default")
      (node (ref "U98") (pin "2") (pinfunction "DOUT_2") (pintype "output"))
      (node (ref "U99") (pin "4") (pinfunction "DIN_4") (pintype "input"))
    )
    (net (code "103") (name "Net-(U100-DIN)") (class "Default")
      (node (ref "U100") (pin "4") (pinfunction "DIN_4") (pintype "input"))
      (node (ref "U99") (pin "2") (pinfunction "DOUT_2") (pintype "output"))
    )
    (net (code "104") (name "Net-(U100-DOUT)") (class "Default")
      (node (ref "U100") (pin "2") (pinfunction "DOUT_2") (pintype "output"))
      (node (ref "U101") (pin "4") (pinfunction "DIN_4") (pintype "input"))
    )
    (net (code "105") (name "Net-(U101-DOUT)") (class "Default")
      (node (ref "U101") (pin "2") (pinfunction "DOUT_2") (pintype "output"))
      (node (ref "U102") (pin "4") (pinfunction "DIN_4") (pintype "input"))
    )
    (net (code "106") (name "Net-(U102-DOUT)") (class "Default")
      (node (ref "U102") (pin "2") (pinfunction "DOUT_2") (pintype "output"))
      (node (ref "U103") (pin "4") (pinfunction "DIN_4") (pintype "input"))
    )
    (net (code "107") (name "Net-(U103-DOUT)") (class "Default")
      (node (ref "U103") (pin "2") (pinfunction "DOUT_2") (pintype "output"))
      (node (ref "U104") (pin "4") (pinfunction "DIN_4") (pintype "input"))
    )
    (net (code "108") (name "Net-(U104-DOUT)") (class "Default")
      (node (ref "U104") (pin "2") (pinfunction "DOUT_2") (pintype "output"))
      (node (ref "U105") (pin "4") (pinfunction "DIN_4") (pintype "input"))
    )
    (net (code "109") (name "Net-(U105-DOUT)") (class "Default")
      (node (ref "U105") (pin "2") (pinfunction "DOUT_2") (pintype "output"))
      (node (ref "U106") (pin "4") (pinfunction "DIN_4") (pintype "input"))
    )
    (net (code "110") (name "Net-(U106-DOUT)") (class "Default")
      (node (ref "U106") (pin "2") (pinfunction "DOUT_2") (pintype "output"))
      (node (ref "U107") (pin "4") (pinfunction "DIN_4") (pintype "input"))
    )
    (net (code "111") (name "Net-(U107-DOUT)") (class "Default")
      (node (ref "U107") (pin "2") (pinfunction "DOUT_2") (pintype "output"))
      (node (ref "U108") (pin "4") (pinfunction "DIN_4") (pintype "input"))
    )
    (net (code "112") (name "Net-(U108-DOUT)") (class "Default")
      (node (ref "U108") (pin "2") (pinfunction "DOUT_2") (pintype "output"))
      (node (ref "U109") (pin "4") (pinfunction "DIN_4") (pintype "input"))
    )
    (net (code "113") (name "Net-(U109-DOUT)") (class "Default")
      (node (ref "U109") (pin "2") (pinfunction "DOUT_2") (pintype "output"))
      (node (ref "U110") (pin "4") (pinfunction "DIN_4") (pintype "input"))
    )
    (net (code "114") (name "Net-(U110-DOUT)") (class "Default")
      (node (ref "U110") (pin "2") (pinfunction "DOUT_2") (pintype "output"))
      (node (ref "U111") (pin "4") (pinfunction "DIN_4") (pintype "input"))
    )
    (net (code "115") (name "Net-(U111-DOUT)") (class "Default")
      (node (ref "U111") (pin "2") (pinfunction "DOUT_2") (pintype "output"))
      (node (ref "U112") (pin "4") (pinfunction "DIN_4") (pintype "input"))
    )
    (net (code "116") (name "Net-(U112-DOUT)") (class "Default")
      (node (ref "U112") (pin "2") (pinfunction "DOUT_2") (pintype "output"))
      (node (ref "U113") (pin "4") (pinfunction "DIN_4") (pintype "input"))
    )
    (net (code "117") (name "Net-(U113-DOUT)") (class "Default")
      (node (ref "U113") (pin "2") (pinfunction "DOUT_2") (pintype "output"))
      (node (ref "U114") (pin "4") (pinfunction "DIN_4") (pintype "input"))
    )
    (net (code "118") (name "Net-(U114-DOUT)") (class "Default")
      (node (ref "U114") (pin "2") (pinfunction "DOUT_2") (pintype "output"))
      (node (ref "U115") (pin "4") (pinfunction "DIN_4") (pintype "input"))
    )
    (net (code "119") (name "Net-(U115-DOUT)") (class "Default")
      (node (ref "U115") (pin "2") (pinfunction "DOUT_2") (pintype "output"))
      (node (ref "U116") (pin "4") (pinfunction "DIN_4") (pintype "input"))
    )
    (net (code "120") (name "Net-(U116-DOUT)") (class "Default")
      (node (ref "U116") (pin "2") (pinfunction "DOUT_2") (pintype "output"))
      (node (ref "U117") (pin "4") (pinfunction "DIN_4") (pintype "input"))
    )
    (net (code "121") (name "Net-(U117-DOUT)") (class "Default")
      (node (ref "U117") (pin "2") (pinfunction "DOUT_2") (pintype "output"))
      (node (ref "U118") (pin "4") (pinfunction "DIN_4") (pintype "input"))
    )
    (net (code "122") (name "Net-(U118-DOUT)") (class "Default")
      (node (ref "U118") (pin "2") (pinfunction "DOUT_2") (pintype "output"))
      (node (ref "U119") (pin "4") (pinfunction "DIN_4") (pintype "input"))
    )
    (net (code "123") (name "Net-(U119-DOUT)") (class "Default")
      (node (ref "U119") (pin "2") (pinfunction "DOUT_2") (pintype "output"))
      (node (ref "U120") (pin "4") (pinfunction "DIN_4") (pintype "input"))
    )
    (net (code "124") (name "Net-(U120-DOUT)") (class "Default")
      (node (ref "U120") (pin "2") (pinfunction "DOUT_2") (pintype "output"))
      (node (ref "U121") (pin "4") (pinfunction "DIN_4") (pintype "input"))
    )
    (net (code "125") (name "Net-(U121-DOUT)") (class "Default")
      (node (ref "U121") (pin "2") (pinfunction "DOUT_2") (pintype "output"))
      (node (ref "U122") (pin "4") (pinfunction "DIN_4") (pintype "input"))
    )
    (net (code "126") (name "Net-(U122-DOUT)") (class "Default")
      (node (ref "U122") (pin "2") (pinfunction "DOUT_2") (pintype "output"))
      (node (ref "U123") (pin "4") (pinfunction "DIN_4") (pintype "input"))
    )
    (net (code "127") (name "Net-(U123-DOUT)") (class "Default")
      (node (ref "U123") (pin "2") (pinfunction "DOUT_2") (pintype "output"))
      (node (ref "U124") (pin "4") (pinfunction "DIN_4") (pintype "input"))
    )
    (net (code "128") (name "Net-(U124-DOUT)") (class "Default")
      (node (ref "U124") (pin "2") (pinfunction "DOUT_2") (pintype "output"))
      (node (ref "U125") (pin "4") (pinfunction "DIN_4") (pintype "input"))
    )
    (net (code "129") (name "Net-(U125-DOUT)") (class "Default")
      (node (ref "U125") (pin "2") (pinfunction "DOUT_2") (pintype "output"))
      (node (ref "U126") (pin "4") (pinfunction "DIN_4") (pintype "input"))
    )
    (net (code "130") (name "Net-(U126-DOUT)") (class "Default")
      (node (ref "U126") (pin "2") (pinfunction "DOUT_2") (pintype "output"))
      (node (ref "U127") (pin "4") (pinfunction "DIN_4") (pintype "input"))
    )
    (net (code "131") (name "Net-(U127-DOUT)") (class "Default")
      (node (ref "U127") (pin "2") (pinfunction "DOUT_2") (pintype "output"))
      (node (ref "U128") (pin "4") (pinfunction "DIN_4") (pintype "input"))
    )
    (net (code "132") (name "Net-(U128-DOUT)") (class "Default")
      (node (ref "U128") (pin "2") (pinfunction "DOUT_2") (pintype "output"))
      (node (ref "U129") (pin "4") (pinfunction "DIN_4") (pintype "input"))
    )
    (net (code "133") (name "Net-(U129-DOUT)") (class "Default")
      (node (ref "U129") (pin "2") (pinfunction "DOUT_2") (pintype "output"))
      (node (ref "U130") (pin "4") (pinfunction "DIN_4") (pintype "input"))
    )
    (net (code "134") (name "Net-(U130-DOUT)") (class "Default")
      (node (ref "U130") (pin "2") (pinfunction "DOUT_2") (pintype "output"))
      (node (ref "U131") (pin "4") (pinfunction "DIN_4") (pintype "input"))
    )
    (net (code "135") (name "Net-(U131-DOUT)") (class "Default")
      (node (ref "U131") (pin "2") (pinfunction "DOUT_2") (pintype "output"))
      (node (ref "U132") (pin "4") (pinfunction "DIN_4") (pintype "input"))
    )
    (net (code "136") (name "Net-(U132-DOUT)") (class "Default")
      (node (ref "U132") (pin "2") (pinfunction "DOUT_2") (pintype "output"))
      (node (ref "U133") (pin "4") (pinfunction "DIN_4") (pintype "input"))
    )
    (net (code "137") (name "Net-(U133-DOUT)") (class "Default")
      (node (ref "U133") (pin "2") (pinfunction "DOUT_2") (pintype "output"))
      (node (ref "U134") (pin "4") (pinfunction "DIN_4") (pintype "input"))
    )
    (net (code "138") (name "Net-(U134-DOUT)") (class "Default")
      (node (ref "U134") (pin "2") (pinfunction "DOUT_2") (pintype "output"))
      (node (ref "U135") (pin "4") (pinfunction "DIN_4") (pintype "input"))
    )
    (net (code "139") (name "Net-(U135-DOUT)") (class "Default")
      (node (ref "U135") (pin "2") (pinfunction "DOUT_2") (pintype "output"))
      (node (ref "U136") (pin "4") (pinfunction "DIN_4") (pintype "input"))
    )
    (net (code "140") (name "Net-(U136-DOUT)") (class "Default")
      (node (ref "U136") (pin "2") (pinfunction "DOUT_2") (pintype "output"))
      (node (ref "U137") (pin "4") (pinfunction "DIN_4") (pintype "input"))
    )
    (net (code "141") (name "Net-(U137-DOUT)") (class "Default")
      (node (ref "U137") (pin "2") (pinfunction "DOUT_2") (pintype "output"))
      (node (ref "U138") (pin "4") (pinfunction "DIN_4") (pintype "input"))
    )
    (net (code "142") (name "Net-(U138-DOUT)") (class "Default")
      (node (ref "U138") (pin "2") (pinfunction "DOUT_2") (pintype "output"))
      (node (ref "U139") (pin "4") (pinfunction "DIN_4") (pintype "input"))
    )
    (net (code "143") (name "Net-(U139-DOUT)") (class "Default")
      (node (ref "U139") (pin "2") (pinfunction "DOUT_2") (pintype "output"))
      (node (ref "U140") (pin "4") (pinfunction "DIN_4") (pintype "input"))
    )
    (net (code "144") (name "Net-(U140-DOUT)") (class "Default")
      (node (ref "U140") (pin "2") (pinfunction "DOUT_2") (pintype "output"))
      (node (ref "U141") (pin "4") (pinfunction "DIN_4") (pintype "input"))
    )
    (net (code "145") (name "unconnected-(U141-DOUT-Pad2)") (class "Default")
      (node (ref "U141") (pin "2") (pinfunction "DOUT_2") (pintype "output+no_connect"))
    )
  )
)
